# Monitor.net
KiCad netlist of a schematic drawn in EAGLE
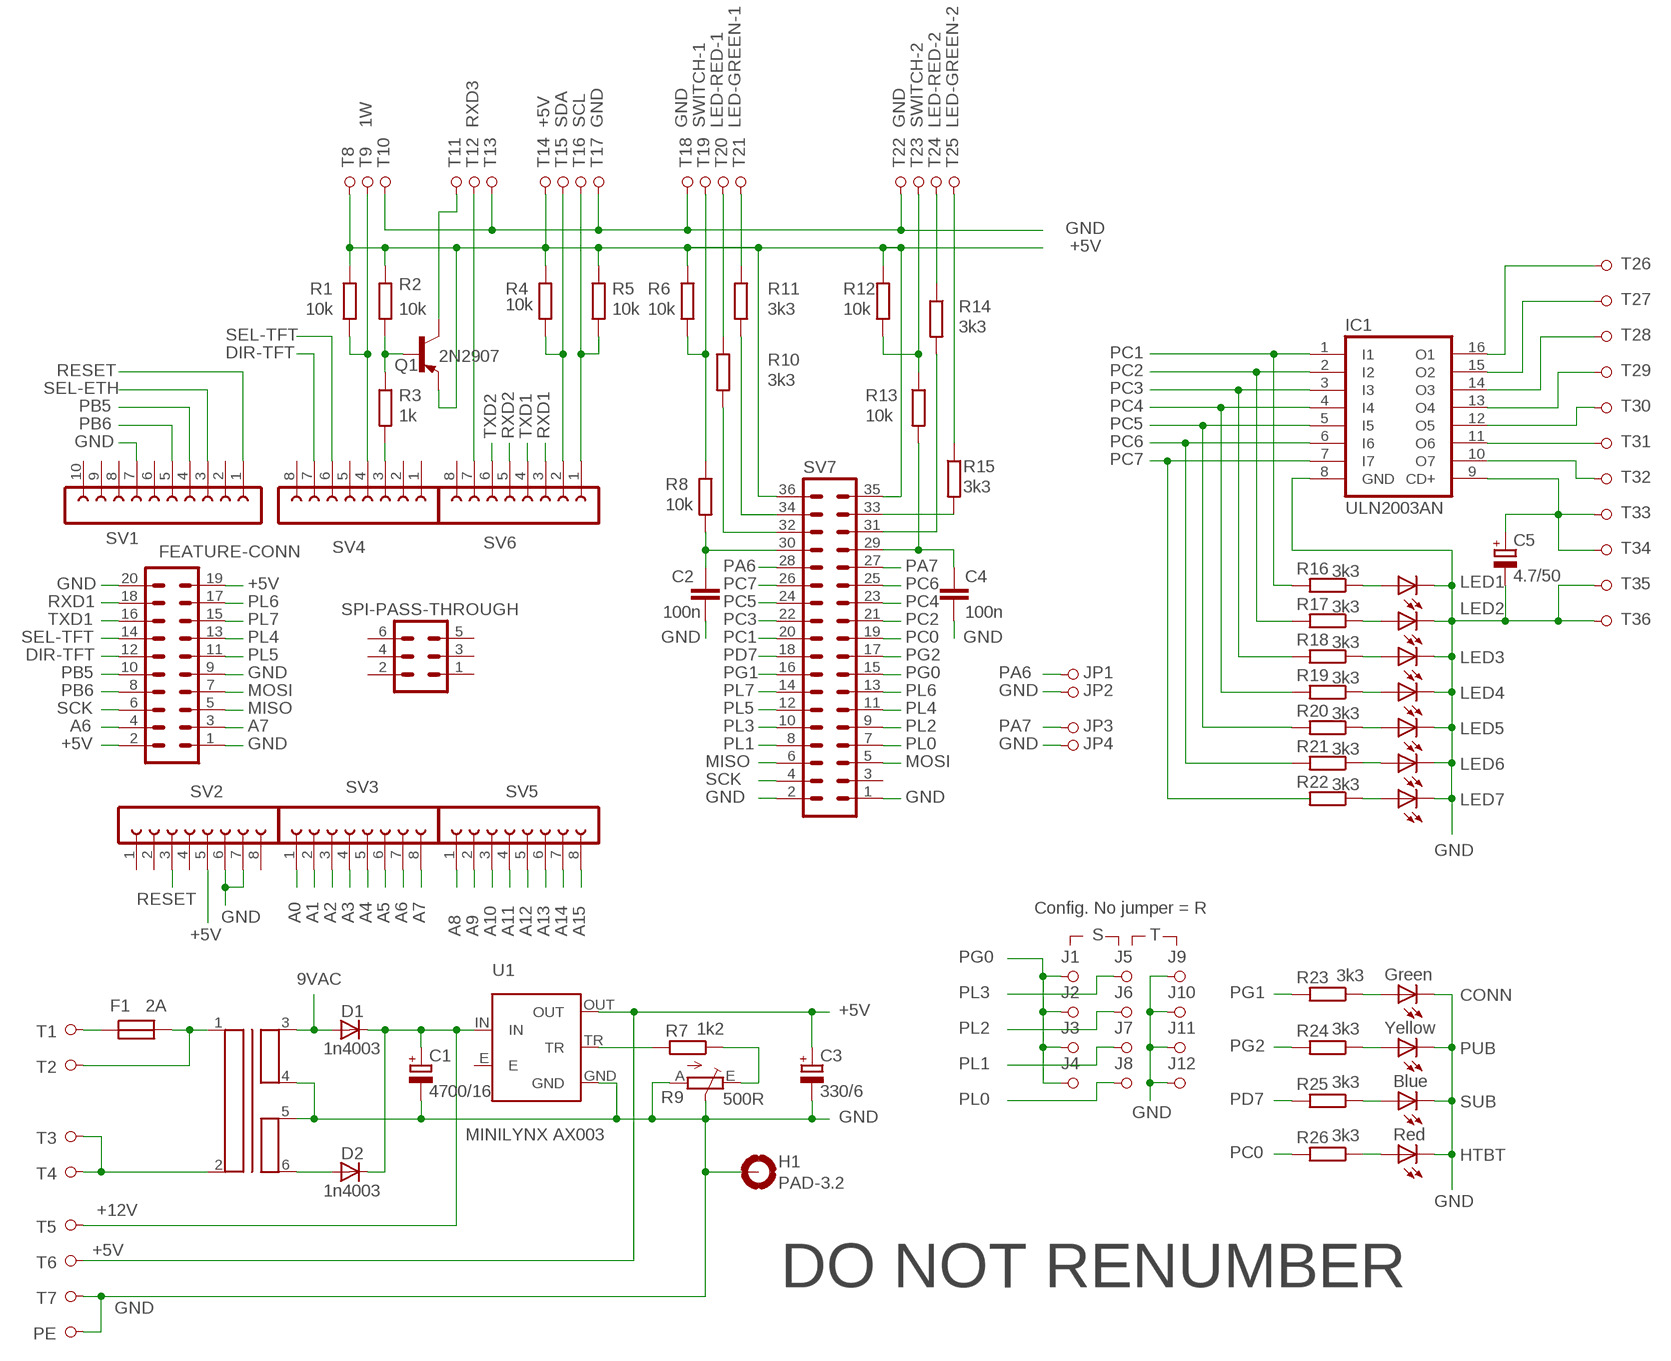
[diagram p0: schematic, sheet 1]
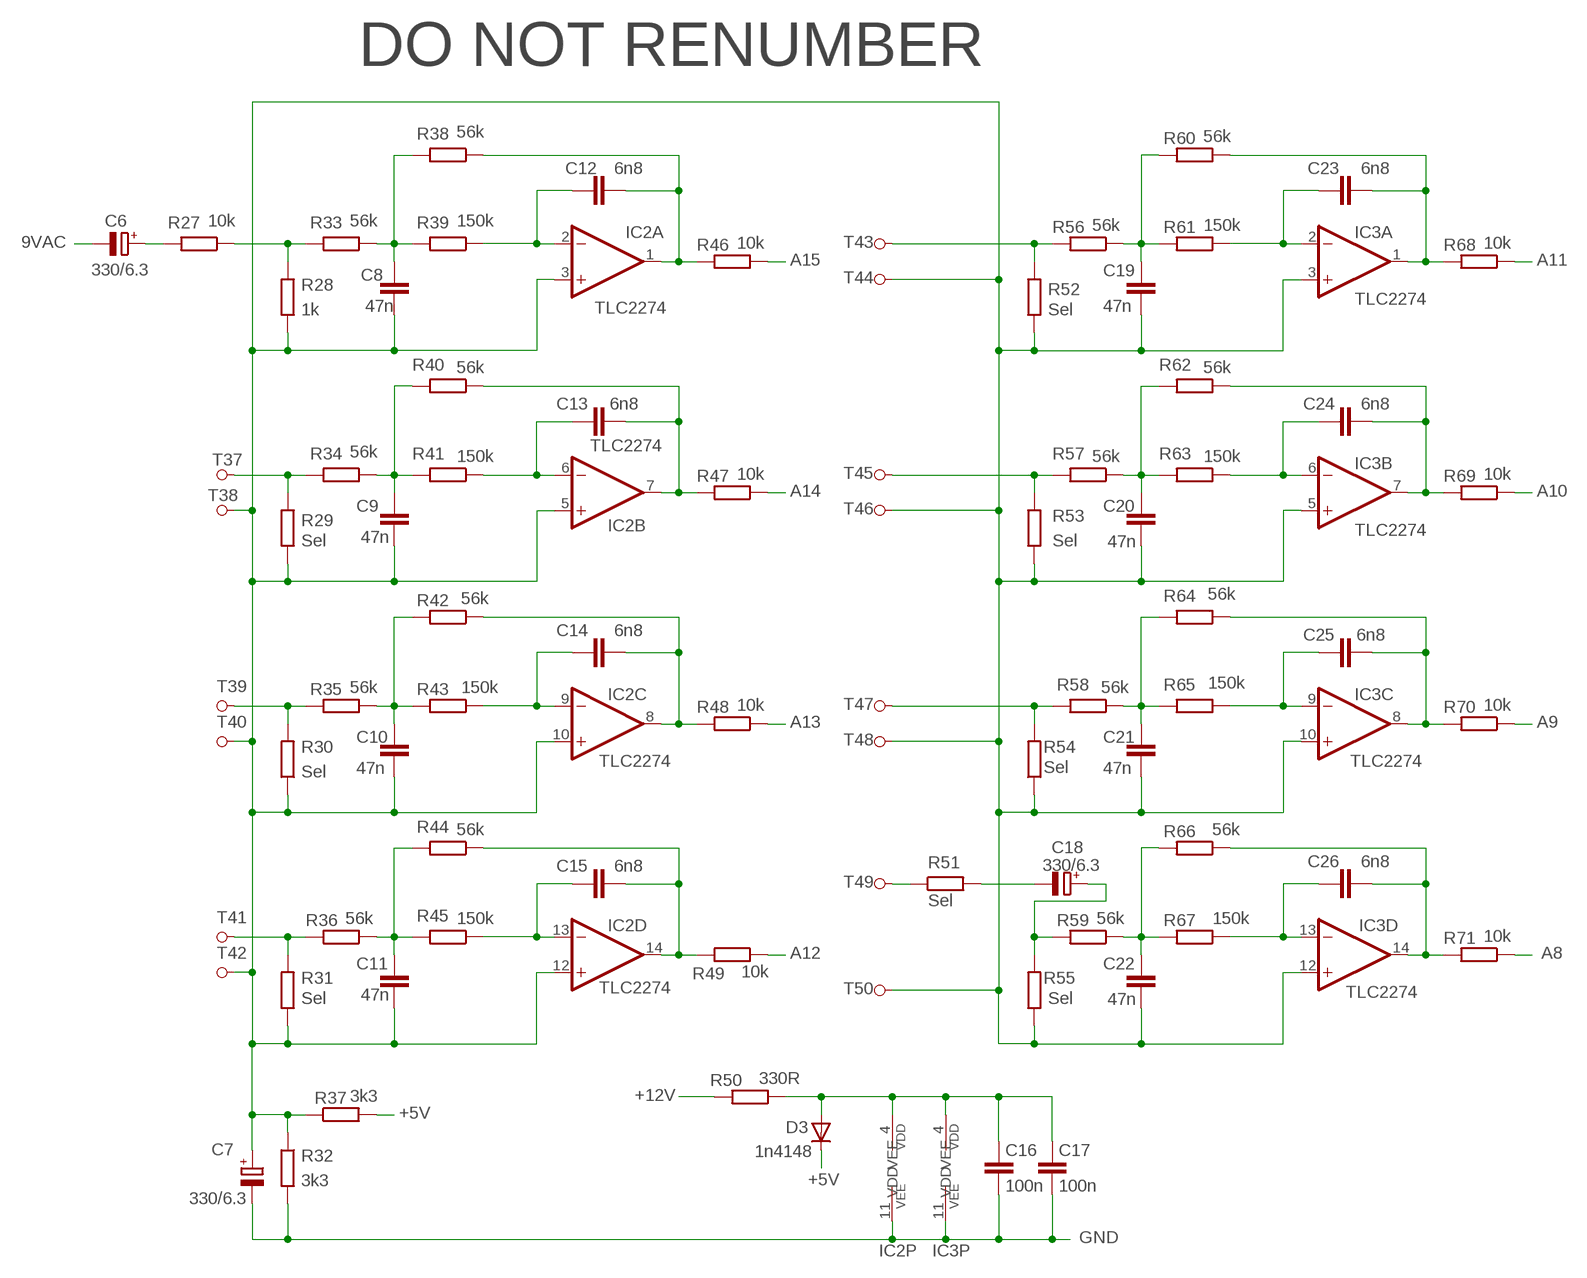
[diagram p1: schematic, sheet 2]

(export (version "E")
  (design (tool "Eeschema 10.0.6"))
  (components
    (comp (ref "C6")
      (value "330/6.3")
      (footprint "eagle-import:E2,5-7")
      (libsource (lib "eagle-import") (part "CPOL-EUE2.5-7"))
    )
    (comp (ref "C7")
      (value "330/6.3")
      (footprint "eagle-import:E2,5-7")
      (libsource (lib "eagle-import") (part "CPOL-EUE2.5-7"))
    )
    (comp (ref "C8")
      (value "47n")
      (footprint "eagle-import:C050-025X075")
      (libsource (lib "eagle-import") (part "C-EU050-025X075"))
    )
    (comp (ref "C9")
      (value "47n")
      (footprint "eagle-import:C050-025X075")
      (libsource (lib "eagle-import") (part "C-EU050-025X075"))
    )
    (comp (ref "C10")
      (value "47n")
      (footprint "eagle-import:C050-025X075")
      (libsource (lib "eagle-import") (part "C-EU050-025X075"))
    )
    (comp (ref "C11")
      (value "47n")
      (footprint "eagle-import:C050-025X075")
      (libsource (lib "eagle-import") (part "C-EU050-025X075"))
    )
    (comp (ref "C12")
      (value "6n8")
      (footprint "eagle-import:C050-025X075")
      (libsource (lib "eagle-import") (part "C-EU050-025X075"))
    )
    (comp (ref "C13")
      (value "6n8")
      (footprint "eagle-import:C050-025X075")
      (libsource (lib "eagle-import") (part "C-EU050-025X075"))
    )
    (comp (ref "C14")
      (value "6n8")
      (footprint "eagle-import:C050-025X075")
      (libsource (lib "eagle-import") (part "C-EU050-025X075"))
    )
    (comp (ref "C15")
      (value "6n8")
      (footprint "eagle-import:C050-025X075")
      (libsource (lib "eagle-import") (part "C-EU050-025X075"))
    )
    (comp (ref "C16")
      (value "100n")
      (footprint "eagle-import:C050-024X044")
      (libsource (lib "eagle-import") (part "C-EU050-024X044"))
    )
    (comp (ref "C17")
      (value "100n")
      (footprint "eagle-import:C050-024X044")
      (libsource (lib "eagle-import") (part "C-EU050-024X044"))
    )
    (comp (ref "C18")
      (value "330/6.3")
      (footprint "eagle-import:E2,5-7")
      (libsource (lib "eagle-import") (part "CPOL-EUE2.5-7"))
    )
    (comp (ref "C19")
      (value "47n")
      (footprint "eagle-import:C050-025X075")
      (libsource (lib "eagle-import") (part "C-EU050-025X075"))
    )
    (comp (ref "C20")
      (value "47n")
      (footprint "eagle-import:C050-025X075")
      (libsource (lib "eagle-import") (part "C-EU050-025X075"))
    )
    (comp (ref "C21")
      (value "47n")
      (footprint "eagle-import:C050-025X075")
      (libsource (lib "eagle-import") (part "C-EU050-025X075"))
    )
    (comp (ref "C22")
      (value "47n")
      (footprint "eagle-import:C050-025X075")
      (libsource (lib "eagle-import") (part "C-EU050-025X075"))
    )
    (comp (ref "C23")
      (value "6n8")
      (footprint "eagle-import:C050-025X075")
      (libsource (lib "eagle-import") (part "C-EU050-025X075"))
    )
    (comp (ref "C24")
      (value "6n8")
      (footprint "eagle-import:C050-025X075")
      (libsource (lib "eagle-import") (part "C-EU050-025X075"))
    )
    (comp (ref "C25")
      (value "6n8")
      (footprint "eagle-import:C050-025X075")
      (libsource (lib "eagle-import") (part "C-EU050-025X075"))
    )
    (comp (ref "C26")
      (value "6n8")
      (footprint "eagle-import:C050-025X075")
      (libsource (lib "eagle-import") (part "C-EU050-025X075"))
    )
    (comp (ref "D3")
      (value "1n4148")
      (footprint "eagle-import:DO34Z7")
      (libsource (lib "eagle-import") (part "1N4148"))
    )
    (comp (ref "IC2")
      (value "TLC2274")
      (footprint "eagle-import:DIL14")
      (libsource (lib "eagle-import") (part "LM124NC"))
    )
    (comp (ref "IC3")
      (value "TLC2274")
      (footprint "eagle-import:DIL14")
      (libsource (lib "eagle-import") (part "LM124NC"))
    )
    (comp (ref "R27")
      (value "10k")
      (footprint "eagle-import:0207_10")
      (libsource (lib "eagle-import") (part "R-EU_0207/10"))
    )
    (comp (ref "R28")
      (value "1k")
      (footprint "eagle-import:0207_10")
      (libsource (lib "eagle-import") (part "R-EU_0207/10"))
    )
    (comp (ref "R29")
      (value "Sel")
      (footprint "eagle-import:0207_10")
      (libsource (lib "eagle-import") (part "R-EU_0207/10"))
    )
    (comp (ref "R30")
      (value "Sel")
      (footprint "eagle-import:0207_10")
      (libsource (lib "eagle-import") (part "R-EU_0207/10"))
    )
    (comp (ref "R31")
      (value "Sel")
      (footprint "eagle-import:0207_10")
      (libsource (lib "eagle-import") (part "R-EU_0207/10"))
    )
    (comp (ref "R32")
      (value "3k3")
      (footprint "eagle-import:0207_10")
      (libsource (lib "eagle-import") (part "R-EU_0207/10"))
    )
    (comp (ref "R33")
      (value "56k")
      (footprint "eagle-import:0207_10")
      (libsource (lib "eagle-import") (part "R-EU_0207/10"))
    )
    (comp (ref "R34")
      (value "56k")
      (footprint "eagle-import:0207_10")
      (libsource (lib "eagle-import") (part "R-EU_0207/10"))
    )
    (comp (ref "R35")
      (value "56k")
      (footprint "eagle-import:0207_10")
      (libsource (lib "eagle-import") (part "R-EU_0207/10"))
    )
    (comp (ref "R36")
      (value "56k")
      (footprint "eagle-import:0207_10")
      (libsource (lib "eagle-import") (part "R-EU_0207/10"))
    )
    (comp (ref "R37")
      (value "3k3")
      (footprint "eagle-import:0207_10")
      (libsource (lib "eagle-import") (part "R-EU_0207/10"))
    )
    (comp (ref "R38")
      (value "56k")
      (footprint "eagle-import:0207_10")
      (libsource (lib "eagle-import") (part "R-EU_0207/10"))
    )
    (comp (ref "R39")
      (value "150k")
      (footprint "eagle-import:0207_10")
      (libsource (lib "eagle-import") (part "R-EU_0207/10"))
    )
    (comp (ref "R40")
      (value "56k")
      (footprint "eagle-import:0207_10")
      (libsource (lib "eagle-import") (part "R-EU_0207/10"))
    )
    (comp (ref "R41")
      (value "150k")
      (footprint "eagle-import:0207_10")
      (libsource (lib "eagle-import") (part "R-EU_0207/10"))
    )
    (comp (ref "R42")
      (value "56k")
      (footprint "eagle-import:0207_10")
      (libsource (lib "eagle-import") (part "R-EU_0207/10"))
    )
    (comp (ref "R43")
      (value "150k")
      (footprint "eagle-import:0207_10")
      (libsource (lib "eagle-import") (part "R-EU_0207/10"))
    )
    (comp (ref "R44")
      (value "56k")
      (footprint "eagle-import:0207_10")
      (libsource (lib "eagle-import") (part "R-EU_0207/10"))
    )
    (comp (ref "R45")
      (value "150k")
      (footprint "eagle-import:0207_10")
      (libsource (lib "eagle-import") (part "R-EU_0207/10"))
    )
    (comp (ref "R46")
      (value "10k")
      (footprint "eagle-import:0207_10")
      (libsource (lib "eagle-import") (part "R-EU_0207/10"))
    )
    (comp (ref "R47")
      (value "10k")
      (footprint "eagle-import:0207_10")
      (libsource (lib "eagle-import") (part "R-EU_0207/10"))
    )
    (comp (ref "R48")
      (value "10k")
      (footprint "eagle-import:0207_10")
      (libsource (lib "eagle-import") (part "R-EU_0207/10"))
    )
    (comp (ref "R49")
      (value "10k")
      (footprint "eagle-import:0207_10")
      (libsource (lib "eagle-import") (part "R-EU_0207/10"))
    )
    (comp (ref "R50")
      (value "330R")
      (footprint "eagle-import:0207_10")
      (libsource (lib "eagle-import") (part "R-EU_0207/10"))
    )
    (comp (ref "R51")
      (value "Sel")
      (footprint "eagle-import:0207_10")
      (libsource (lib "eagle-import") (part "R-EU_0207/10"))
    )
    (comp (ref "R52")
      (value "Sel")
      (footprint "eagle-import:0207_10")
      (libsource (lib "eagle-import") (part "R-EU_0207/10"))
    )
    (comp (ref "R53")
      (value "Sel")
      (footprint "eagle-import:0207_10")
      (libsource (lib "eagle-import") (part "R-EU_0207/10"))
    )
    (comp (ref "R54")
      (value "Sel")
      (footprint "eagle-import:0207_10")
      (libsource (lib "eagle-import") (part "R-EU_0207/10"))
    )
    (comp (ref "R55")
      (value "Sel")
      (footprint "eagle-import:0207_10")
      (libsource (lib "eagle-import") (part "R-EU_0207/10"))
    )
    (comp (ref "R56")
      (value "56k")
      (footprint "eagle-import:0207_10")
      (libsource (lib "eagle-import") (part "R-EU_0207/10"))
    )
    (comp (ref "R57")
      (value "56k")
      (footprint "eagle-import:0207_10")
      (libsource (lib "eagle-import") (part "R-EU_0207/10"))
    )
    (comp (ref "R58")
      (value "56k")
      (footprint "eagle-import:0207_10")
      (libsource (lib "eagle-import") (part "R-EU_0207/10"))
    )
    (comp (ref "R59")
      (value "56k")
      (footprint "eagle-import:0207_10")
      (libsource (lib "eagle-import") (part "R-EU_0207/10"))
    )
    (comp (ref "R60")
      (value "56k")
      (footprint "eagle-import:0207_10")
      (libsource (lib "eagle-import") (part "R-EU_0207/10"))
    )
    (comp (ref "R61")
      (value "150k")
      (footprint "eagle-import:0207_10")
      (libsource (lib "eagle-import") (part "R-EU_0207/10"))
    )
    (comp (ref "R62")
      (value "56k")
      (footprint "eagle-import:0207_10")
      (libsource (lib "eagle-import") (part "R-EU_0207/10"))
    )
    (comp (ref "R63")
      (value "150k")
      (footprint "eagle-import:0207_10")
      (libsource (lib "eagle-import") (part "R-EU_0207/10"))
    )
    (comp (ref "R64")
      (value "56k")
      (footprint "eagle-import:0207_10")
      (libsource (lib "eagle-import") (part "R-EU_0207/10"))
    )
    (comp (ref "R65")
      (value "150k")
      (footprint "eagle-import:0207_10")
      (libsource (lib "eagle-import") (part "R-EU_0207/10"))
    )
    (comp (ref "R66")
      (value "56k")
      (footprint "eagle-import:0207_10")
      (libsource (lib "eagle-import") (part "R-EU_0207/10"))
    )
    (comp (ref "R67")
      (value "150k")
      (footprint "eagle-import:0207_10")
      (libsource (lib "eagle-import") (part "R-EU_0207/10"))
    )
    (comp (ref "R68")
      (value "10k")
      (footprint "eagle-import:0207_10")
      (libsource (lib "eagle-import") (part "R-EU_0207/10"))
    )
    (comp (ref "R69")
      (value "10k")
      (footprint "eagle-import:0207_10")
      (libsource (lib "eagle-import") (part "R-EU_0207/10"))
    )
    (comp (ref "R70")
      (value "10k")
      (footprint "eagle-import:0207_10")
      (libsource (lib "eagle-import") (part "R-EU_0207/10"))
    )
    (comp (ref "R71")
      (value "10k")
      (footprint "eagle-import:0207_10")
      (libsource (lib "eagle-import") (part "R-EU_0207/10"))
    )
    (comp (ref "T37")
      (value "PINHDR-1X1")
      (footprint "eagle-import:HDR1X1")
      (libsource (lib "eagle-import") (part "PINHDR-1X1"))
    )
    (comp (ref "T38")
      (value "PINHDR-1X1")
      (footprint "eagle-import:HDR1X1")
      (libsource (lib "eagle-import") (part "PINHDR-1X1"))
    )
    (comp (ref "T39")
      (value "PINHDR-1X1")
      (footprint "eagle-import:HDR1X1")
      (libsource (lib "eagle-import") (part "PINHDR-1X1"))
    )
    (comp (ref "T40")
      (value "PINHDR-1X1")
      (footprint "eagle-import:HDR1X1")
      (libsource (lib "eagle-import") (part "PINHDR-1X1"))
    )
    (comp (ref "T41")
      (value "PINHDR-1X1")
      (footprint "eagle-import:HDR1X1")
      (libsource (lib "eagle-import") (part "PINHDR-1X1"))
    )
    (comp (ref "T42")
      (value "PINHDR-1X1")
      (footprint "eagle-import:HDR1X1")
      (libsource (lib "eagle-import") (part "PINHDR-1X1"))
    )
    (comp (ref "T43")
      (value "PINHDR-1X1")
      (footprint "eagle-import:HDR1X1")
      (libsource (lib "eagle-import") (part "PINHDR-1X1"))
    )
    (comp (ref "T44")
      (value "PINHDR-1X1")
      (footprint "eagle-import:HDR1X1")
      (libsource (lib "eagle-import") (part "PINHDR-1X1"))
    )
    (comp (ref "T45")
      (value "PINHDR-1X1")
      (footprint "eagle-import:HDR1X1")
      (libsource (lib "eagle-import") (part "PINHDR-1X1"))
    )
    (comp (ref "T46")
      (value "PINHDR-1X1")
      (footprint "eagle-import:HDR1X1")
      (libsource (lib "eagle-import") (part "PINHDR-1X1"))
    )
    (comp (ref "T47")
      (value "PINHDR-1X1")
      (footprint "eagle-import:HDR1X1")
      (libsource (lib "eagle-import") (part "PINHDR-1X1"))
    )
    (comp (ref "T48")
      (value "PINHDR-1X1")
      (footprint "eagle-import:HDR1X1")
      (libsource (lib "eagle-import") (part "PINHDR-1X1"))
    )
    (comp (ref "T49")
      (value "PINHDR-1X1")
      (footprint "eagle-import:HDR1X1")
      (libsource (lib "eagle-import") (part "PINHDR-1X1"))
    )
    (comp (ref "T50")
      (value "PINHDR-1X1")
      (footprint "eagle-import:HDR1X1")
      (libsource (lib "eagle-import") (part "PINHDR-1X1"))
    )
    (comp (ref "C1")
      (value "4700/16")
      (footprint "eagle-import:E7,5-16")
      (libsource (lib "eagle-import") (part "CPOL-EUE7.5-16"))
    )
    (comp (ref "C2")
      (value "100n")
      (footprint "eagle-import:C050-024X044")
      (libsource (lib "eagle-import") (part "C-EU050-024X044"))
    )
    (comp (ref "C3")
      (value "330/6")
      (footprint "eagle-import:E2,5-7")
      (libsource (lib "eagle-import") (part "CPOL-EUE2.5-7"))
    )
    (comp (ref "C4")
      (value "100n")
      (footprint "eagle-import:C050-024X044")
      (libsource (lib "eagle-import") (part "C-EU050-024X044"))
    )
    (comp (ref "C5")
      (value "4.7/50")
      (footprint "eagle-import:E5-5")
      (libsource (lib "eagle-import") (part "CPOL-EUE5-5"))
    )
    (comp (ref "CONN")
      (value "Green")
      (footprint "eagle-import:LED3MM")
      (libsource (lib "eagle-import") (part "LED3MM"))
    )
    (comp (ref "D1")
      (value "1n4003")
      (footprint "eagle-import:DO34Z7")
      (libsource (lib "eagle-import") (part "1N4148"))
    )
    (comp (ref "D2")
      (value "1n4003")
      (footprint "eagle-import:DO34Z7")
      (libsource (lib "eagle-import") (part "1N4148"))
    )
    (comp (ref "F1")
      (value "2A")
      (footprint "eagle-import:FX0456")
      (libsource (lib "eagle-import") (part "FX0456-ZEKERING"))
    )
    (comp (ref "FEATURE-CONN")
      (value "PINHD-10X2")
      (footprint "eagle-import:MA10-2")
      (libsource (lib "eagle-import") (part "PINHD-10X2"))
    )
    (comp (ref "H1")
      (value "PAD-3.2")
      (footprint "eagle-import:3,2-PAD")
      (libsource (lib "eagle-import") (part "MOUNT-PAD-ROUND3.2"))
    )
    (comp (ref "HTBT")
      (value "Red")
      (footprint "eagle-import:LED3MM")
      (libsource (lib "eagle-import") (part "LED3MM"))
    )
    (comp (ref "IC1")
      (value "ULN2003AN")
      (footprint "eagle-import:DIL16")
      (libsource (lib "eagle-import") (part "ULN2003AN"))
    )
    (comp (ref "J1")
      (value "PINHDR-1X1")
      (footprint "eagle-import:HDR1X1")
      (libsource (lib "eagle-import") (part "PINHDR-1X1"))
    )
    (comp (ref "J2")
      (value "PINHDR-1X1")
      (footprint "eagle-import:HDR1X1")
      (libsource (lib "eagle-import") (part "PINHDR-1X1"))
    )
    (comp (ref "J3")
      (value "PINHDR-1X1")
      (footprint "eagle-import:HDR1X1")
      (libsource (lib "eagle-import") (part "PINHDR-1X1"))
    )
    (comp (ref "J4")
      (value "PINHDR-1X1")
      (footprint "eagle-import:HDR1X1")
      (libsource (lib "eagle-import") (part "PINHDR-1X1"))
    )
    (comp (ref "J5")
      (value "PINHDR-1X1")
      (footprint "eagle-import:HDR1X1")
      (libsource (lib "eagle-import") (part "PINHDR-1X1"))
    )
    (comp (ref "J6")
      (value "PINHDR-1X1")
      (footprint "eagle-import:HDR1X1")
      (libsource (lib "eagle-import") (part "PINHDR-1X1"))
    )
    (comp (ref "J7")
      (value "PINHDR-1X1")
      (footprint "eagle-import:HDR1X1")
      (libsource (lib "eagle-import") (part "PINHDR-1X1"))
    )
    (comp (ref "J8")
      (value "PINHDR-1X1")
      (footprint "eagle-import:HDR1X1")
      (libsource (lib "eagle-import") (part "PINHDR-1X1"))
    )
    (comp (ref "J9")
      (value "PINHDR-1X1")
      (footprint "eagle-import:HDR1X1")
      (libsource (lib "eagle-import") (part "PINHDR-1X1"))
    )
    (comp (ref "J10")
      (value "PINHDR-1X1")
      (footprint "eagle-import:HDR1X1")
      (libsource (lib "eagle-import") (part "PINHDR-1X1"))
    )
    (comp (ref "J11")
      (value "PINHDR-1X1")
      (footprint "eagle-import:HDR1X1")
      (libsource (lib "eagle-import") (part "PINHDR-1X1"))
    )
    (comp (ref "J12")
      (value "PINHDR-1X1")
      (footprint "eagle-import:HDR1X1")
      (libsource (lib "eagle-import") (part "PINHDR-1X1"))
    )
    (comp (ref "JP1")
      (value "PINHDR-1X1")
      (footprint "eagle-import:HDR1X1")
      (libsource (lib "eagle-import") (part "PINHDR-1X1"))
    )
    (comp (ref "JP2")
      (value "PINHDR-1X1")
      (footprint "eagle-import:HDR1X1")
      (libsource (lib "eagle-import") (part "PINHDR-1X1"))
    )
    (comp (ref "JP3")
      (value "PINHDR-1X1")
      (footprint "eagle-import:HDR1X1")
      (libsource (lib "eagle-import") (part "PINHDR-1X1"))
    )
    (comp (ref "JP4")
      (value "PINHDR-1X1")
      (footprint "eagle-import:HDR1X1")
      (libsource (lib "eagle-import") (part "PINHDR-1X1"))
    )
    (comp (ref "LED1")
      (value "LED3MM")
      (footprint "eagle-import:LED3MM")
      (libsource (lib "eagle-import") (part "LED3MM"))
    )
    (comp (ref "LED2")
      (value "LED3MM")
      (footprint "eagle-import:LED3MM")
      (libsource (lib "eagle-import") (part "LED3MM"))
    )
    (comp (ref "LED3")
      (value "LED3MM")
      (footprint "eagle-import:LED3MM")
      (libsource (lib "eagle-import") (part "LED3MM"))
    )
    (comp (ref "LED4")
      (value "LED3MM")
      (footprint "eagle-import:LED3MM")
      (libsource (lib "eagle-import") (part "LED3MM"))
    )
    (comp (ref "LED5")
      (value "LED3MM")
      (footprint "eagle-import:LED3MM")
      (libsource (lib "eagle-import") (part "LED3MM"))
    )
    (comp (ref "LED6")
      (value "LED3MM")
      (footprint "eagle-import:LED3MM")
      (libsource (lib "eagle-import") (part "LED3MM"))
    )
    (comp (ref "LED7")
      (value "LED3MM")
      (footprint "eagle-import:LED3MM")
      (libsource (lib "eagle-import") (part "LED3MM"))
    )
    (comp (ref "PE")
      (value "PINHDR-1X1")
      (footprint "eagle-import:HDR1X1")
      (libsource (lib "eagle-import") (part "PINHDR-1X1"))
    )
    (comp (ref "PUB")
      (value "Yellow")
      (footprint "eagle-import:LED3MM")
      (libsource (lib "eagle-import") (part "LED3MM"))
    )
    (comp (ref "Q1")
      (value "2N2907")
      (footprint "eagle-import:TO39")
      (libsource (lib "eagle-import") (part "PNP-TO39"))
    )
    (comp (ref "R1")
      (value "10k")
      (footprint "eagle-import:0207_10")
      (libsource (lib "eagle-import") (part "R-EU_0207/10"))
    )
    (comp (ref "R2")
      (value "10k")
      (footprint "eagle-import:0207_10")
      (libsource (lib "eagle-import") (part "R-EU_0207/10"))
    )
    (comp (ref "R3")
      (value "1k")
      (footprint "eagle-import:0207_10")
      (libsource (lib "eagle-import") (part "R-EU_0207/10"))
    )
    (comp (ref "R4")
      (value "10k")
      (footprint "eagle-import:0207_10")
      (libsource (lib "eagle-import") (part "R-EU_0207/10"))
    )
    (comp (ref "R5")
      (value "10k")
      (footprint "eagle-import:0207_10")
      (libsource (lib "eagle-import") (part "R-EU_0207/10"))
    )
    (comp (ref "R6")
      (value "10k")
      (footprint "eagle-import:0207_10")
      (libsource (lib "eagle-import") (part "R-EU_0207/10"))
    )
    (comp (ref "R7")
      (value "1k2")
      (footprint "eagle-import:0207_10")
      (libsource (lib "eagle-import") (part "R-EU_0207/10"))
    )
    (comp (ref "R8")
      (value "10k")
      (footprint "eagle-import:0207_10")
      (libsource (lib "eagle-import") (part "R-EU_0207/10"))
    )
    (comp (ref "R9")
      (value "500R")
      (footprint "eagle-import:TRIMPOT-4")
      (libsource (lib "eagle-import") (part "TRIMPOT-4"))
    )
    (comp (ref "R10")
      (value "3k3")
      (footprint "eagle-import:0207_10")
      (libsource (lib "eagle-import") (part "R-EU_0207/10"))
    )
    (comp (ref "R11")
      (value "3k3")
      (footprint "eagle-import:0207_10")
      (libsource (lib "eagle-import") (part "R-EU_0207/10"))
    )
    (comp (ref "R12")
      (value "10k")
      (footprint "eagle-import:0207_10")
      (libsource (lib "eagle-import") (part "R-EU_0207/10"))
    )
    (comp (ref "R13")
      (value "10k")
      (footprint "eagle-import:0207_10")
      (libsource (lib "eagle-import") (part "R-EU_0207/10"))
    )
    (comp (ref "R14")
      (value "3k3")
      (footprint "eagle-import:0207_10")
      (libsource (lib "eagle-import") (part "R-EU_0207/10"))
    )
    (comp (ref "R15")
      (value "3k3")
      (footprint "eagle-import:0207_10")
      (libsource (lib "eagle-import") (part "R-EU_0207/10"))
    )
    (comp (ref "R16")
      (value "3k3")
      (footprint "eagle-import:0207_10")
      (libsource (lib "eagle-import") (part "R-EU_0207/10"))
    )
    (comp (ref "R17")
      (value "3k3")
      (footprint "eagle-import:0207_10")
      (libsource (lib "eagle-import") (part "R-EU_0207/10"))
    )
    (comp (ref "R18")
      (value "3k3")
      (footprint "eagle-import:0207_10")
      (libsource (lib "eagle-import") (part "R-EU_0207/10"))
    )
    (comp (ref "R19")
      (value "3k3")
      (footprint "eagle-import:0207_10")
      (libsource (lib "eagle-import") (part "R-EU_0207/10"))
    )
    (comp (ref "R20")
      (value "3k3")
      (footprint "eagle-import:0207_10")
      (libsource (lib "eagle-import") (part "R-EU_0207/10"))
    )
    (comp (ref "R21")
      (value "3k3")
      (footprint "eagle-import:0207_10")
      (libsource (lib "eagle-import") (part "R-EU_0207/10"))
    )
    (comp (ref "R22")
      (value "3k3")
      (footprint "eagle-import:0207_10")
      (libsource (lib "eagle-import") (part "R-EU_0207/10"))
    )
    (comp (ref "R23")
      (value "3k3")
      (footprint "eagle-import:0207_10")
      (libsource (lib "eagle-import") (part "R-EU_0207/10"))
    )
    (comp (ref "R24")
      (value "3k3")
      (footprint "eagle-import:0207_10")
      (libsource (lib "eagle-import") (part "R-EU_0207/10"))
    )
    (comp (ref "R25")
      (value "3k3")
      (footprint "eagle-import:0207_10")
      (libsource (lib "eagle-import") (part "R-EU_0207/10"))
    )
    (comp (ref "R26")
      (value "3k3")
      (footprint "eagle-import:0207_10")
      (libsource (lib "eagle-import") (part "R-EU_0207/10"))
    )
    (comp (ref "SPI-PASS-THROUGH")
      (value "PINHD-3X2")
      (footprint "eagle-import:MA03-2")
      (libsource (lib "eagle-import") (part "PINHD-3X2"))
    )
    (comp (ref "SUB")
      (value "Blue")
      (footprint "eagle-import:LED3MM")
      (libsource (lib "eagle-import") (part "LED3MM"))
    )
    (comp (ref "SV1")
      (value "FE10-1")
      (footprint "eagle-import:FE10")
      (libsource (lib "eagle-import") (part "FE10-1"))
    )
    (comp (ref "SV2")
      (value "FE08-1")
      (footprint "eagle-import:FE08")
      (libsource (lib "eagle-import") (part "FE08-1"))
    )
    (comp (ref "SV3")
      (value "FE08-1")
      (footprint "eagle-import:FE08")
      (libsource (lib "eagle-import") (part "FE08-1"))
    )
    (comp (ref "SV4")
      (value "FE08-1")
      (footprint "eagle-import:FE08")
      (libsource (lib "eagle-import") (part "FE08-1"))
    )
    (comp (ref "SV5")
      (value "FE08-1")
      (footprint "eagle-import:FE08")
      (libsource (lib "eagle-import") (part "FE08-1"))
    )
    (comp (ref "SV6")
      (value "FE08-1")
      (footprint "eagle-import:FE08")
      (libsource (lib "eagle-import") (part "FE08-1"))
    )
    (comp (ref "SV7")
      (value "PINHD-18X2")
      (footprint "eagle-import:MA18-2")
      (libsource (lib "eagle-import") (part "PINHD-18X2"))
    )
    (comp (ref "T1")
      (value "PINHDR-1X1")
      (footprint "eagle-import:HDR1X1")
      (libsource (lib "eagle-import") (part "PINHDR-1X1"))
    )
    (comp (ref "T2")
      (value "PINHDR-1X1")
      (footprint "eagle-import:HDR1X1")
      (libsource (lib "eagle-import") (part "PINHDR-1X1"))
    )
    (comp (ref "T3")
      (value "PINHDR-1X1")
      (footprint "eagle-import:HDR1X1")
      (libsource (lib "eagle-import") (part "PINHDR-1X1"))
    )
    (comp (ref "T4")
      (value "PINHDR-1X1")
      (footprint "eagle-import:HDR1X1")
      (libsource (lib "eagle-import") (part "PINHDR-1X1"))
    )
    (comp (ref "T5")
      (value "PINHDR-1X1")
      (footprint "eagle-import:HDR1X1")
      (libsource (lib "eagle-import") (part "PINHDR-1X1"))
    )
    (comp (ref "T6")
      (value "PINHDR-1X1")
      (footprint "eagle-import:HDR1X1")
      (libsource (lib "eagle-import") (part "PINHDR-1X1"))
    )
    (comp (ref "T7")
      (value "PINHDR-1X1")
      (footprint "eagle-import:HDR1X1")
      (libsource (lib "eagle-import") (part "PINHDR-1X1"))
    )
    (comp (ref "T8")
      (value "PINHDR-1X1")
      (footprint "eagle-import:HDR1X1")
      (libsource (lib "eagle-import") (part "PINHDR-1X1"))
    )
    (comp (ref "T9")
      (value "PINHDR-1X1")
      (footprint "eagle-import:HDR1X1")
      (libsource (lib "eagle-import") (part "PINHDR-1X1"))
    )
    (comp (ref "T10")
      (value "PINHDR-1X1")
      (footprint "eagle-import:HDR1X1")
      (libsource (lib "eagle-import") (part "PINHDR-1X1"))
    )
    (comp (ref "T11")
      (value "PINHDR-1X1")
      (footprint "eagle-import:HDR1X1")
      (libsource (lib "eagle-import") (part "PINHDR-1X1"))
    )
    (comp (ref "T12")
      (value "PINHDR-1X1")
      (footprint "eagle-import:HDR1X1")
      (libsource (lib "eagle-import") (part "PINHDR-1X1"))
    )
    (comp (ref "T13")
      (value "PINHDR-1X1")
      (footprint "eagle-import:HDR1X1")
      (libsource (lib "eagle-import") (part "PINHDR-1X1"))
    )
    (comp (ref "T14")
      (value "PINHDR-1X1")
      (footprint "eagle-import:HDR1X1")
      (libsource (lib "eagle-import") (part "PINHDR-1X1"))
    )
    (comp (ref "T15")
      (value "PINHDR-1X1")
      (footprint "eagle-import:HDR1X1")
      (libsource (lib "eagle-import") (part "PINHDR-1X1"))
    )
    (comp (ref "T16")
      (value "PINHDR-1X1")
      (footprint "eagle-import:HDR1X1")
      (libsource (lib "eagle-import") (part "PINHDR-1X1"))
    )
    (comp (ref "T17")
      (value "PINHDR-1X1")
      (footprint "eagle-import:HDR1X1")
      (libsource (lib "eagle-import") (part "PINHDR-1X1"))
    )
    (comp (ref "T18")
      (value "PINHDR-1X1")
      (footprint "eagle-import:HDR1X1")
      (libsource (lib "eagle-import") (part "PINHDR-1X1"))
    )
    (comp (ref "T19")
      (value "PINHDR-1X1")
      (footprint "eagle-import:HDR1X1")
      (libsource (lib "eagle-import") (part "PINHDR-1X1"))
    )
    (comp (ref "T20")
      (value "PINHDR-1X1")
      (footprint "eagle-import:HDR1X1")
      (libsource (lib "eagle-import") (part "PINHDR-1X1"))
    )
    (comp (ref "T21")
      (value "PINHDR-1X1")
      (footprint "eagle-import:HDR1X1")
      (libsource (lib "eagle-import") (part "PINHDR-1X1"))
    )
    (comp (ref "T22")
      (value "PINHDR-1X1")
      (footprint "eagle-import:HDR1X1")
      (libsource (lib "eagle-import") (part "PINHDR-1X1"))
    )
    (comp (ref "T23")
      (value "PINHDR-1X1")
      (footprint "eagle-import:HDR1X1")
      (libsource (lib "eagle-import") (part "PINHDR-1X1"))
    )
    (comp (ref "T24")
      (value "PINHDR-1X1")
      (footprint "eagle-import:HDR1X1")
      (libsource (lib "eagle-import") (part "PINHDR-1X1"))
    )
    (comp (ref "T25")
      (value "PINHDR-1X1")
      (footprint "eagle-import:HDR1X1")
      (libsource (lib "eagle-import") (part "PINHDR-1X1"))
    )
    (comp (ref "T26")
      (value "PINHDR-1X1")
      (footprint "eagle-import:HDR1X1")
      (libsource (lib "eagle-import") (part "PINHDR-1X1"))
    )
    (comp (ref "T27")
      (value "PINHDR-1X1")
      (footprint "eagle-import:HDR1X1")
      (libsource (lib "eagle-import") (part "PINHDR-1X1"))
    )
    (comp (ref "T28")
      (value "PINHDR-1X1")
      (footprint "eagle-import:HDR1X1")
      (libsource (lib "eagle-import") (part "PINHDR-1X1"))
    )
    (comp (ref "T29")
      (value "PINHDR-1X1")
      (footprint "eagle-import:HDR1X1")
      (libsource (lib "eagle-import") (part "PINHDR-1X1"))
    )
    (comp (ref "T30")
      (value "PINHDR-1X1")
      (footprint "eagle-import:HDR1X1")
      (libsource (lib "eagle-import") (part "PINHDR-1X1"))
    )
    (comp (ref "T31")
      (value "PINHDR-1X1")
      (footprint "eagle-import:HDR1X1")
      (libsource (lib "eagle-import") (part "PINHDR-1X1"))
    )
    (comp (ref "T32")
      (value "PINHDR-1X1")
      (footprint "eagle-import:HDR1X1")
      (libsource (lib "eagle-import") (part "PINHDR-1X1"))
    )
    (comp (ref "T33")
      (value "PINHDR-1X1")
      (footprint "eagle-import:HDR1X1")
      (libsource (lib "eagle-import") (part "PINHDR-1X1"))
    )
    (comp (ref "T34")
      (value "PINHDR-1X1")
      (footprint "eagle-import:HDR1X1")
      (libsource (lib "eagle-import") (part "PINHDR-1X1"))
    )
    (comp (ref "T35")
      (value "PINHDR-1X1")
      (footprint "eagle-import:HDR1X1")
      (libsource (lib "eagle-import") (part "PINHDR-1X1"))
    )
    (comp (ref "T36")
      (value "PINHDR-1X1")
      (footprint "eagle-import:HDR1X1")
      (libsource (lib "eagle-import") (part "PINHDR-1X1"))
    )
    (comp (ref "TR1")
      (value "TRAFO")
      (footprint "eagle-import:TRAFO")
      (libsource (lib "eagle-import") (part "TRAFO"))
    )
    (comp (ref "U1")
      (value "MINILYNX AX003")
      (footprint "eagle-import:MINILYNX")
      (libsource (lib "eagle-import") (part "MINILYNX"))
    )
  )
  (nets
    (net (code "1") (name "+5V") (class "Default")
      (node (ref "C3") (pin "+") (pinfunction "+_+") (pintype "passive"))
      (node (ref "D3") (pin "C") (pinfunction "C_C") (pintype "passive"))
      (node (ref "FEATURE-CONN") (pin "19") (pinfunction "19_19") (pintype "passive"))
      (node (ref "FEATURE-CONN") (pin "2") (pinfunction "2_2") (pintype "passive"))
      (node (ref "Q1") (pin "1") (pinfunction "E_1") (pintype "passive"))
      (node (ref "R1") (pin "1") (pinfunction "1_1") (pintype "passive"))
      (node (ref "R12") (pin "1") (pinfunction "1_1") (pintype "passive"))
      (node (ref "R2") (pin "1") (pinfunction "1_1") (pintype "passive"))
      (node (ref "R37") (pin "2") (pinfunction "2_2") (pintype "passive"))
      (node (ref "R4") (pin "1") (pinfunction "1_1") (pintype "passive"))
      (node (ref "R5") (pin "1") (pinfunction "1_1") (pintype "passive"))
      (node (ref "R6") (pin "1") (pinfunction "1_1") (pintype "passive"))
      (node (ref "SV2") (pin "5") (pinfunction "5_5") (pintype "passive"))
      (node (ref "SV7") (pin "35") (pinfunction "35_35") (pintype "passive"))
      (node (ref "SV7") (pin "36") (pinfunction "36_36") (pintype "passive"))
      (node (ref "T14") (pin "1") (pinfunction "._1") (pintype "passive"))
      (node (ref "T6") (pin "1") (pinfunction "._1") (pintype "passive"))
      (node (ref "T8") (pin "1") (pinfunction "._1") (pintype "passive"))
      (node (ref "U1") (pin "OUT") (pinfunction "OUT_OUT") (pintype "output"))
    )
    (net (code "2") (name "+12V") (class "Default")
      (node (ref "C1") (pin "+") (pinfunction "+_+") (pintype "passive"))
      (node (ref "D1") (pin "C") (pinfunction "C_C") (pintype "passive"))
      (node (ref "D2") (pin "C") (pinfunction "C_C") (pintype "passive"))
      (node (ref "R50") (pin "2") (pinfunction "2_2") (pintype "passive"))
      (node (ref "T5") (pin "1") (pinfunction "._1") (pintype "passive"))
      (node (ref "U1") (pin "IN") (pinfunction "IN_IN") (pintype "power_in"))
    )
    (net (code "3") (name "1W") (class "Default")
      (node (ref "R1") (pin "2") (pinfunction "2_2") (pintype "passive"))
      (node (ref "SV4") (pin "4") (pinfunction "4_4") (pintype "passive"))
      (node (ref "T9") (pin "1") (pinfunction "._1") (pintype "passive"))
    )
    (net (code "4") (name "9VAC") (class "Default")
      (node (ref "C6") (pin "-") (pinfunction "-_-") (pintype "passive"))
      (node (ref "D1") (pin "A") (pinfunction "A_A") (pintype "passive"))
      (node (ref "TR1") (pin "3") (pinfunction "3_3") (pintype "bidirectional"))
    )
    (net (code "5") (name "A0") (class "Default")
      (node (ref "SV3") (pin "1") (pinfunction "1_1") (pintype "passive"))
    )
    (net (code "6") (name "A1") (class "Default")
      (node (ref "SV3") (pin "2") (pinfunction "2_2") (pintype "passive"))
    )
    (net (code "7") (name "A2") (class "Default")
      (node (ref "SV3") (pin "3") (pinfunction "3_3") (pintype "passive"))
    )
    (net (code "8") (name "A3") (class "Default")
      (node (ref "SV3") (pin "4") (pinfunction "4_4") (pintype "passive"))
    )
    (net (code "9") (name "A4") (class "Default")
      (node (ref "SV3") (pin "5") (pinfunction "5_5") (pintype "passive"))
    )
    (net (code "10") (name "A5") (class "Default")
      (node (ref "SV3") (pin "6") (pinfunction "6_6") (pintype "passive"))
    )
    (net (code "11") (name "A6") (class "Default")
      (node (ref "FEATURE-CONN") (pin "4") (pinfunction "4_4") (pintype "passive"))
      (node (ref "SV3") (pin "7") (pinfunction "7_7") (pintype "passive"))
    )
    (net (code "12") (name "A7") (class "Default")
      (node (ref "FEATURE-CONN") (pin "3") (pinfunction "3_3") (pintype "passive"))
      (node (ref "SV3") (pin "8") (pinfunction "8_8") (pintype "passive"))
    )
    (net (code "13") (name "A8") (class "Default")
      (node (ref "R71") (pin "1") (pinfunction "1_1") (pintype "passive"))
      (node (ref "SV5") (pin "1") (pinfunction "1_1") (pintype "passive"))
    )
    (net (code "14") (name "A9") (class "Default")
      (node (ref "R70") (pin "1") (pinfunction "1_1") (pintype "passive"))
      (node (ref "SV5") (pin "2") (pinfunction "2_2") (pintype "passive"))
    )
    (net (code "15") (name "A10") (class "Default")
      (node (ref "R69") (pin "1") (pinfunction "1_1") (pintype "passive"))
      (node (ref "SV5") (pin "3") (pinfunction "3_3") (pintype "passive"))
    )
    (net (code "16") (name "A11") (class "Default")
      (node (ref "R68") (pin "1") (pinfunction "1_1") (pintype "passive"))
      (node (ref "SV5") (pin "4") (pinfunction "4_4") (pintype "passive"))
    )
    (net (code "17") (name "A12") (class "Default")
      (node (ref "R49") (pin "1") (pinfunction "1_1") (pintype "passive"))
      (node (ref "SV5") (pin "5") (pinfunction "5_5") (pintype "passive"))
    )
    (net (code "18") (name "A13") (class "Default")
      (node (ref "R48") (pin "1") (pinfunction "1_1") (pintype "passive"))
      (node (ref "SV5") (pin "6") (pinfunction "6_6") (pintype "passive"))
    )
    (net (code "19") (name "A14") (class "Default")
      (node (ref "R47") (pin "1") (pinfunction "1_1") (pintype "passive"))
      (node (ref "SV5") (pin "7") (pinfunction "7_7") (pintype "passive"))
    )
    (net (code "20") (name "A15") (class "Default")
      (node (ref "R46") (pin "1") (pinfunction "1_1") (pintype "passive"))
      (node (ref "SV5") (pin "8") (pinfunction "8_8") (pintype "passive"))
    )
    (net (code "21") (name "DIR-TFT") (class "Default")
      (node (ref "FEATURE-CONN") (pin "12") (pinfunction "12_12") (pintype "passive"))
      (node (ref "SV4") (pin "7") (pinfunction "7_7") (pintype "passive"))
    )
    (net (code "22") (name "GND") (class "Default")
      (node (ref "C1") (pin "-") (pinfunction "-_-") (pintype "passive"))
      (node (ref "C16") (pin "2") (pinfunction "2_2") (pintype "passive"))
      (node (ref "C17") (pin "2") (pinfunction "2_2") (pintype "passive"))
      (node (ref "C2") (pin "1") (pinfunction "1_1") (pintype "passive"))
      (node (ref "C3") (pin "-") (pinfunction "-_-") (pintype "passive"))
      (node (ref "C4") (pin "2") (pinfunction "2_2") (pintype "passive"))
      (node (ref "C5") (pin "-") (pinfunction "-_-") (pintype "passive"))
      (node (ref "C7") (pin "-") (pinfunction "-_-") (pintype "passive"))
      (node (ref "CONN") (pin "K") (pinfunction "C_K") (pintype "passive"))
      (node (ref "FEATURE-CONN") (pin "1") (pinfunction "1_1") (pintype "passive"))
      (node (ref "FEATURE-CONN") (pin "20") (pinfunction "20_20") (pintype "passive"))
      (node (ref "FEATURE-CONN") (pin "9") (pinfunction "9_9") (pintype "passive"))
      (node (ref "H1") (pin "B3,2") (pinfunction "MOUNT_B3,2") (pintype "passive"))
      (node (ref "HTBT") (pin "K") (pinfunction "C_K") (pintype "passive"))
      (node (ref "IC1") (pin "8") (pinfunction "GND_8") (pintype "power_in"))
      (node (ref "IC2") (pin "11") (pinfunction "VEE_11") (pintype "bidirectional"))
      (node (ref "IC3") (pin "11") (pinfunction "VEE_11") (pintype "bidirectional"))
      (node (ref "J10") (pin "1") (pinfunction "._1") (pintype "passive"))
      (node (ref "J11") (pin "1") (pinfunction "._1") (pintype "passive"))
      (node (ref "J12") (pin "1") (pinfunction "._1") (pintype "passive"))
      (node (ref "J9") (pin "1") (pinfunction "._1") (pintype "passive"))
      (node (ref "JP2") (pin "1") (pinfunction "._1") (pintype "passive"))
      (node (ref "JP4") (pin "1") (pinfunction "._1") (pintype "passive"))
      (node (ref "LED1") (pin "K") (pinfunction "C_K") (pintype "passive"))
      (node (ref "LED2") (pin "K") (pinfunction "C_K") (pintype "passive"))
      (node (ref "LED3") (pin "K") (pinfunction "C_K") (pintype "passive"))
      (node (ref "LED4") (pin "K") (pinfunction "C_K") (pintype "passive"))
      (node (ref "LED5") (pin "K") (pinfunction "C_K") (pintype "passive"))
      (node (ref "LED6") (pin "K") (pinfunction "C_K") (pintype "passive"))
      (node (ref "LED7") (pin "K") (pinfunction "C_K") (pintype "passive"))
      (node (ref "PE") (pin "1") (pinfunction "._1") (pintype "passive"))
      (node (ref "PUB") (pin "K") (pinfunction "C_K") (pintype "passive"))
      (node (ref "R32") (pin "2") (pinfunction "2_2") (pintype "passive"))
      (node (ref "R9") (pin "A") (pinfunction "A_A") (pintype "passive"))
      (node (ref "R9") (pin "S1") (pinfunction "S_S1") (pintype "passive"))
      (node (ref "R9") (pin "S2") (pinfunction "S_S2") (pintype "passive"))
      (node (ref "SUB") (pin "K") (pinfunction "C_K") (pintype "passive"))
      (node (ref "SV1") (pin "7") (pinfunction "7_7") (pintype "passive"))
      (node (ref "SV2") (pin "6") (pinfunction "6_6") (pintype "passive"))
      (node (ref "SV2") (pin "7") (pinfunction "7_7") (pintype "passive"))
      (node (ref "SV7") (pin "1") (pinfunction "1_1") (pintype "passive"))
      (node (ref "SV7") (pin "2") (pinfunction "2_2") (pintype "passive"))
      (node (ref "T10") (pin "1") (pinfunction "._1") (pintype "passive"))
      (node (ref "T13") (pin "1") (pinfunction "._1") (pintype "passive"))
      (node (ref "T17") (pin "1") (pinfunction "._1") (pintype "passive"))
      (node (ref "T18") (pin "1") (pinfunction "._1") (pintype "passive"))
      (node (ref "T22") (pin "1") (pinfunction "._1") (pintype "passive"))
      (node (ref "T35") (pin "1") (pinfunction "._1") (pintype "passive"))
      (node (ref "T36") (pin "1") (pinfunction "._1") (pintype "passive"))
      (node (ref "T7") (pin "1") (pinfunction "._1") (pintype "passive"))
      (node (ref "TR1") (pin "4") (pinfunction "4_4") (pintype "bidirectional"))
      (node (ref "TR1") (pin "5") (pinfunction "5_5") (pintype "bidirectional"))
      (node (ref "U1") (pin "GND") (pinfunction "GND_GND") (pintype "power_in"))
    )
    (net (code "23") (name "LED-GREEN-1") (class "Default")
      (node (ref "R11") (pin "1") (pinfunction "1_1") (pintype "passive"))
      (node (ref "T21") (pin "1") (pinfunction "._1") (pintype "passive"))
    )
    (net (code "24") (name "LED-GREEN-2") (class "Default")
      (node (ref "R15") (pin "1") (pinfunction "1_1") (pintype "passive"))
      (node (ref "T25") (pin "1") (pinfunction "._1") (pintype "passive"))
    )
    (net (code "25") (name "LED-RED-1") (class "Default")
      (node (ref "R10") (pin "1") (pinfunction "1_1") (pintype "passive"))
      (node (ref "T20") (pin "1") (pinfunction "._1") (pintype "passive"))
    )
    (net (code "26") (name "LED-RED-2") (class "Default")
      (node (ref "R14") (pin "1") (pinfunction "1_1") (pintype "passive"))
      (node (ref "T24") (pin "1") (pinfunction "._1") (pintype "passive"))
    )
    (net (code "27") (name "MISO") (class "Default")
      (node (ref "FEATURE-CONN") (pin "5") (pinfunction "5_5") (pintype "passive"))
      (node (ref "SV7") (pin "6") (pinfunction "6_6") (pintype "passive"))
    )
    (net (code "28") (name "MOSI") (class "Default")
      (node (ref "FEATURE-CONN") (pin "7") (pinfunction "7_7") (pintype "passive"))
      (node (ref "SV7") (pin "5") (pinfunction "5_5") (pintype "passive"))
    )
    (net (code "29") (name "Net-(C2-Pad2)") (class "Default")
      (node (ref "C2") (pin "2") (pinfunction "2_2") (pintype "passive"))
      (node (ref "R8") (pin "2") (pinfunction "2_2") (pintype "passive"))
      (node (ref "SV7") (pin "30") (pinfunction "30_30") (pintype "passive"))
    )
    (net (code "30") (name "Net-(C4-Pad1)") (class "Default")
      (node (ref "C4") (pin "1") (pinfunction "1_1") (pintype "passive"))
      (node (ref "R13") (pin "2") (pinfunction "2_2") (pintype "passive"))
      (node (ref "SV7") (pin "29") (pinfunction "29_29") (pintype "passive"))
    )
    (net (code "31") (name "Net-(C6-Pad+)") (class "Default")
      (node (ref "C6") (pin "+") (pinfunction "+_+") (pintype "passive"))
      (node (ref "R27") (pin "2") (pinfunction "2_2") (pintype "passive"))
    )
    (net (code "32") (name "Net-(C8-Pad1)") (class "Default")
      (node (ref "C8") (pin "1") (pinfunction "1_1") (pintype "passive"))
      (node (ref "R33") (pin "1") (pinfunction "1_1") (pintype "passive"))
      (node (ref "R38") (pin "2") (pinfunction "2_2") (pintype "passive"))
      (node (ref "R39") (pin "2") (pinfunction "2_2") (pintype "passive"))
    )
    (net (code "33") (name "Net-(C9-Pad1)") (class "Default")
      (node (ref "C9") (pin "1") (pinfunction "1_1") (pintype "passive"))
      (node (ref "R34") (pin "1") (pinfunction "1_1") (pintype "passive"))
      (node (ref "R40") (pin "2") (pinfunction "2_2") (pintype "passive"))
      (node (ref "R41") (pin "2") (pinfunction "2_2") (pintype "passive"))
    )
    (net (code "34") (name "Net-(C10-Pad1)") (class "Default")
      (node (ref "C10") (pin "1") (pinfunction "1_1") (pintype "passive"))
      (node (ref "R35") (pin "1") (pinfunction "1_1") (pintype "passive"))
      (node (ref "R42") (pin "2") (pinfunction "2_2") (pintype "passive"))
      (node (ref "R43") (pin "2") (pinfunction "2_2") (pintype "passive"))
    )
    (net (code "35") (name "Net-(C11-Pad1)") (class "Default")
      (node (ref "C11") (pin "1") (pinfunction "1_1") (pintype "passive"))
      (node (ref "R36") (pin "1") (pinfunction "1_1") (pintype "passive"))
      (node (ref "R44") (pin "2") (pinfunction "2_2") (pintype "passive"))
      (node (ref "R45") (pin "2") (pinfunction "2_2") (pintype "passive"))
    )
    (net (code "36") (name "Net-(C18-Pad+)") (class "Default")
      (node (ref "C18") (pin "+") (pinfunction "+_+") (pintype "passive"))
      (node (ref "R55") (pin "2") (pinfunction "2_2") (pintype "passive"))
      (node (ref "R59") (pin "2") (pinfunction "2_2") (pintype "passive"))
    )
    (net (code "37") (name "Net-(C18-Pad-)") (class "Default")
      (node (ref "C18") (pin "-") (pinfunction "-_-") (pintype "passive"))
      (node (ref "R51") (pin "2") (pinfunction "2_2") (pintype "passive"))
    )
    (net (code "38") (name "Net-(C19-Pad1)") (class "Default")
      (node (ref "C19") (pin "1") (pinfunction "1_1") (pintype "passive"))
      (node (ref "R56") (pin "1") (pinfunction "1_1") (pintype "passive"))
      (node (ref "R60") (pin "2") (pinfunction "2_2") (pintype "passive"))
      (node (ref "R61") (pin "2") (pinfunction "2_2") (pintype "passive"))
    )
    (net (code "39") (name "Net-(C20-Pad1)") (class "Default")
      (node (ref "C20") (pin "1") (pinfunction "1_1") (pintype "passive"))
      (node (ref "R57") (pin "1") (pinfunction "1_1") (pintype "passive"))
      (node (ref "R62") (pin "2") (pinfunction "2_2") (pintype "passive"))
      (node (ref "R63") (pin "2") (pinfunction "2_2") (pintype "passive"))
    )
    (net (code "40") (name "Net-(C21-Pad1)") (class "Default")
      (node (ref "C21") (pin "1") (pinfunction "1_1") (pintype "passive"))
      (node (ref "R58") (pin "1") (pinfunction "1_1") (pintype "passive"))
      (node (ref "R64") (pin "2") (pinfunction "2_2") (pintype "passive"))
      (node (ref "R65") (pin "2") (pinfunction "2_2") (pintype "passive"))
    )
    (net (code "41") (name "Net-(C22-Pad1)") (class "Default")
      (node (ref "C22") (pin "1") (pinfunction "1_1") (pintype "passive"))
      (node (ref "R59") (pin "1") (pinfunction "1_1") (pintype "passive"))
      (node (ref "R66") (pin "2") (pinfunction "2_2") (pintype "passive"))
      (node (ref "R67") (pin "2") (pinfunction "2_2") (pintype "passive"))
    )
    (net (code "42") (name "Net-(CONN-PadA)") (class "Default")
      (node (ref "CONN") (pin "A") (pinfunction "A_A") (pintype "passive"))
      (node (ref "R23") (pin "1") (pinfunction "1_1") (pintype "passive"))
    )
    (net (code "43") (name "Net-(D2-PadA)") (class "Default")
      (node (ref "D2") (pin "A") (pinfunction "A_A") (pintype "passive"))
      (node (ref "TR1") (pin "6") (pinfunction "6_6") (pintype "bidirectional"))
    )
    (net (code "44") (name "Net-(F1-1)") (class "Default")
      (node (ref "F1") (pin "P$1") (pinfunction "1_P$1") (pintype "passive"))
      (node (ref "T1") (pin "1") (pinfunction "._1") (pintype "passive"))
    )
    (net (code "45") (name "Net-(F1-2)") (class "Default")
      (node (ref "F1") (pin "P$2") (pinfunction "2_P$2") (pintype "passive"))
      (node (ref "T2") (pin "1") (pinfunction "._1") (pintype "passive"))
      (node (ref "TR1") (pin "1") (pinfunction "1_1") (pintype "bidirectional"))
    )
    (net (code "46") (name "Net-(HTBT-PadA)") (class "Default")
      (node (ref "HTBT") (pin "A") (pinfunction "A_A") (pintype "passive"))
      (node (ref "R26") (pin "1") (pinfunction "1_1") (pintype "passive"))
    )
    (net (code "47") (name "Net-(IC1-CD+)") (class "Default")
      (node (ref "C5") (pin "+") (pinfunction "+_+") (pintype "passive"))
      (node (ref "IC1") (pin "9") (pinfunction "CD+_9") (pintype "passive"))
      (node (ref "T33") (pin "1") (pinfunction "._1") (pintype "passive"))
      (node (ref "T34") (pin "1") (pinfunction "._1") (pintype "passive"))
    )
    (net (code "48") (name "Net-(IC1-O1)") (class "Default")
      (node (ref "IC1") (pin "16") (pinfunction "O1_16") (pintype "open_collector"))
      (node (ref "T26") (pin "1") (pinfunction "._1") (pintype "passive"))
    )
    (net (code "49") (name "Net-(IC1-O2)") (class "Default")
      (node (ref "IC1") (pin "15") (pinfunction "O2_15") (pintype "open_collector"))
      (node (ref "T27") (pin "1") (pinfunction "._1") (pintype "passive"))
    )
    (net (code "50") (name "Net-(IC1-O3)") (class "Default")
      (node (ref "IC1") (pin "14") (pinfunction "O3_14") (pintype "open_collector"))
      (node (ref "T28") (pin "1") (pinfunction "._1") (pintype "passive"))
    )
    (net (code "51") (name "Net-(IC1-O4)") (class "Default")
      (node (ref "IC1") (pin "13") (pinfunction "O4_13") (pintype "open_collector"))
      (node (ref "T29") (pin "1") (pinfunction "._1") (pintype "passive"))
    )
    (net (code "52") (name "Net-(IC1-O5)") (class "Default")
      (node (ref "IC1") (pin "12") (pinfunction "O5_12") (pintype "open_collector"))
      (node (ref "T30") (pin "1") (pinfunction "._1") (pintype "passive"))
    )
    (net (code "53") (name "Net-(IC1-O6)") (class "Default")
      (node (ref "IC1") (pin "11") (pinfunction "O6_11") (pintype "open_collector"))
      (node (ref "T31") (pin "1") (pinfunction "._1") (pintype "passive"))
    )
    (net (code "54") (name "Net-(IC1-O7)") (class "Default")
      (node (ref "IC1") (pin "10") (pinfunction "O7_10") (pintype "open_collector"))
      (node (ref "T32") (pin "1") (pinfunction "._1") (pintype "passive"))
    )
    (net (code "55") (name "Net-(IC2A-+IN)") (class "Default")
      (node (ref "C10") (pin "2") (pinfunction "2_2") (pintype "passive"))
      (node (ref "C11") (pin "2") (pinfunction "2_2") (pintype "passive"))
      (node (ref "C19") (pin "2") (pinfunction "2_2") (pintype "passive"))
      (node (ref "C20") (pin "2") (pinfunction "2_2") (pintype "passive"))
      (node (ref "C21") (pin "2") (pinfunction "2_2") (pintype "passive"))
      (node (ref "C22") (pin "2") (pinfunction "2_2") (pintype "passive"))
      (node (ref "C7") (pin "+") (pinfunction "+_+") (pintype "passive"))
      (node (ref "C8") (pin "2") (pinfunction "2_2") (pintype "passive"))
      (node (ref "C9") (pin "2") (pinfunction "2_2") (pintype "passive"))
      (node (ref "IC2") (pin "10") (pinfunction "+IN_10") (pintype "input"))
      (node (ref "IC2") (pin "12") (pinfunction "+IN_12") (pintype "input"))
      (node (ref "IC2") (pin "3") (pinfunction "+IN_3") (pintype "input"))
      (node (ref "IC2") (pin "5") (pinfunction "+IN_5") (pintype "input"))
      (node (ref "IC3") (pin "10") (pinfunction "+IN_10") (pintype "input"))
      (node (ref "IC3") (pin "12") (pinfunction "+IN_12") (pintype "input"))
      (node (ref "IC3") (pin "3") (pinfunction "+IN_3") (pintype "input"))
      (node (ref "IC3") (pin "5") (pinfunction "+IN_5") (pintype "input"))
      (node (ref "R28") (pin "1") (pinfunction "1_1") (pintype "passive"))
      (node (ref "R29") (pin "1") (pinfunction "1_1") (pintype "passive"))
      (node (ref "R30") (pin "1") (pinfunction "1_1") (pintype "passive"))
      (node (ref "R31") (pin "1") (pinfunction "1_1") (pintype "passive"))
      (node (ref "R32") (pin "1") (pinfunction "1_1") (pintype "passive"))
      (node (ref "R37") (pin "1") (pinfunction "1_1") (pintype "passive"))
      (node (ref "R52") (pin "1") (pinfunction "1_1") (pintype "passive"))
      (node (ref "R53") (pin "1") (pinfunction "1_1") (pintype "passive"))
      (node (ref "R54") (pin "1") (pinfunction "1_1") (pintype "passive"))
      (node (ref "R55") (pin "1") (pinfunction "1_1") (pintype "passive"))
      (node (ref "T38") (pin "1") (pinfunction "._1") (pintype "passive"))
      (node (ref "T40") (pin "1") (pinfunction "._1") (pintype "passive"))
      (node (ref "T42") (pin "1") (pinfunction "._1") (pintype "passive"))
      (node (ref "T44") (pin "1") (pinfunction "._1") (pintype "passive"))
      (node (ref "T46") (pin "1") (pinfunction "._1") (pintype "passive"))
      (node (ref "T48") (pin "1") (pinfunction "._1") (pintype "passive"))
      (node (ref "T50") (pin "1") (pinfunction "._1") (pintype "passive"))
    )
    (net (code "56") (name "Net-(IC2A--IN)") (class "Default")
      (node (ref "C12") (pin "1") (pinfunction "1_1") (pintype "passive"))
      (node (ref "IC2") (pin "2") (pinfunction "-IN_2") (pintype "input"))
      (node (ref "R39") (pin "1") (pinfunction "1_1") (pintype "passive"))
    )
    (net (code "57") (name "Net-(IC2A-OUT)") (class "Default")
      (node (ref "C12") (pin "2") (pinfunction "2_2") (pintype "passive"))
      (node (ref "IC2") (pin "1") (pinfunction "OUT_1") (pintype "output"))
      (node (ref "R38") (pin "1") (pinfunction "1_1") (pintype "passive"))
      (node (ref "R46") (pin "2") (pinfunction "2_2") (pintype "passive"))
    )
    (net (code "58") (name "Net-(IC2B--IN)") (class "Default")
      (node (ref "C13") (pin "1") (pinfunction "1_1") (pintype "passive"))
      (node (ref "IC2") (pin "6") (pinfunction "-IN_6") (pintype "input"))
      (node (ref "R41") (pin "1") (pinfunction "1_1") (pintype "passive"))
    )
    (net (code "59") (name "Net-(IC2B-OUT)") (class "Default")
      (node (ref "C13") (pin "2") (pinfunction "2_2") (pintype "passive"))
      (node (ref "IC2") (pin "7") (pinfunction "OUT_7") (pintype "output"))
      (node (ref "R40") (pin "1") (pinfunction "1_1") (pintype "passive"))
      (node (ref "R47") (pin "2") (pinfunction "2_2") (pintype "passive"))
    )
    (net (code "60") (name "Net-(IC2C--IN)") (class "Default")
      (node (ref "C14") (pin "1") (pinfunction "1_1") (pintype "passive"))
      (node (ref "IC2") (pin "9") (pinfunction "-IN_9") (pintype "input"))
      (node (ref "R43") (pin "1") (pinfunction "1_1") (pintype "passive"))
    )
    (net (code "61") (name "Net-(IC2C-OUT)") (class "Default")
      (node (ref "C14") (pin "2") (pinfunction "2_2") (pintype "passive"))
      (node (ref "IC2") (pin "8") (pinfunction "OUT_8") (pintype "output"))
      (node (ref "R42") (pin "1") (pinfunction "1_1") (pintype "passive"))
      (node (ref "R48") (pin "2") (pinfunction "2_2") (pintype "passive"))
    )
    (net (code "62") (name "Net-(IC2D--IN)") (class "Default")
      (node (ref "C15") (pin "1") (pinfunction "1_1") (pintype "passive"))
      (node (ref "IC2") (pin "13") (pinfunction "-IN_13") (pintype "input"))
      (node (ref "R45") (pin "1") (pinfunction "1_1") (pintype "passive"))
    )
    (net (code "63") (name "Net-(IC2D-OUT)") (class "Default")
      (node (ref "C15") (pin "2") (pinfunction "2_2") (pintype "passive"))
      (node (ref "IC2") (pin "14") (pinfunction "OUT_14") (pintype "output"))
      (node (ref "R44") (pin "1") (pinfunction "1_1") (pintype "passive"))
      (node (ref "R49") (pin "2") (pinfunction "2_2") (pintype "passive"))
    )
    (net (code "64") (name "Net-(IC2E-VDD)") (class "Default")
      (node (ref "C16") (pin "1") (pinfunction "1_1") (pintype "passive"))
      (node (ref "C17") (pin "1") (pinfunction "1_1") (pintype "passive"))
      (node (ref "D3") (pin "A") (pinfunction "A_A") (pintype "passive"))
      (node (ref "IC2") (pin "4") (pinfunction "VDD_4") (pintype "bidirectional"))
      (node (ref "IC3") (pin "4") (pinfunction "VDD_4") (pintype "bidirectional"))
      (node (ref "R50") (pin "1") (pinfunction "1_1") (pintype "passive"))
    )
    (net (code "65") (name "Net-(IC3A--IN)") (class "Default")
      (node (ref "C23") (pin "1") (pinfunction "1_1") (pintype "passive"))
      (node (ref "IC3") (pin "2") (pinfunction "-IN_2") (pintype "input"))
      (node (ref "R61") (pin "1") (pinfunction "1_1") (pintype "passive"))
    )
    (net (code "66") (name "Net-(IC3A-OUT)") (class "Default")
      (node (ref "C23") (pin "2") (pinfunction "2_2") (pintype "passive"))
      (node (ref "IC3") (pin "1") (pinfunction "OUT_1") (pintype "output"))
      (node (ref "R60") (pin "1") (pinfunction "1_1") (pintype "passive"))
      (node (ref "R68") (pin "2") (pinfunction "2_2") (pintype "passive"))
    )
    (net (code "67") (name "Net-(IC3B--IN)") (class "Default")
      (node (ref "C24") (pin "1") (pinfunction "1_1") (pintype "passive"))
      (node (ref "IC3") (pin "6") (pinfunction "-IN_6") (pintype "input"))
      (node (ref "R63") (pin "1") (pinfunction "1_1") (pintype "passive"))
    )
    (net (code "68") (name "Net-(IC3B-OUT)") (class "Default")
      (node (ref "C24") (pin "2") (pinfunction "2_2") (pintype "passive"))
      (node (ref "IC3") (pin "7") (pinfunction "OUT_7") (pintype "output"))
      (node (ref "R62") (pin "1") (pinfunction "1_1") (pintype "passive"))
      (node (ref "R69") (pin "2") (pinfunction "2_2") (pintype "passive"))
    )
    (net (code "69") (name "Net-(IC3C--IN)") (class "Default")
      (node (ref "C25") (pin "1") (pinfunction "1_1") (pintype "passive"))
      (node (ref "IC3") (pin "9") (pinfunction "-IN_9") (pintype "input"))
      (node (ref "R65") (pin "1") (pinfunction "1_1") (pintype "passive"))
    )
    (net (code "70") (name "Net-(IC3C-OUT)") (class "Default")
      (node (ref "C25") (pin "2") (pinfunction "2_2") (pintype "passive"))
      (node (ref "IC3") (pin "8") (pinfunction "OUT_8") (pintype "output"))
      (node (ref "R64") (pin "1") (pinfunction "1_1") (pintype "passive"))
      (node (ref "R70") (pin "2") (pinfunction "2_2") (pintype "passive"))
    )
    (net (code "71") (name "Net-(IC3D--IN)") (class "Default")
      (node (ref "C26") (pin "1") (pinfunction "1_1") (pintype "passive"))
      (node (ref "IC3") (pin "13") (pinfunction "-IN_13") (pintype "input"))
      (node (ref "R67") (pin "1") (pinfunction "1_1") (pintype "passive"))
    )
    (net (code "72") (name "Net-(IC3D-OUT)") (class "Default")
      (node (ref "C26") (pin "2") (pinfunction "2_2") (pintype "passive"))
      (node (ref "IC3") (pin "14") (pinfunction "OUT_14") (pintype "output"))
      (node (ref "R66") (pin "1") (pinfunction "1_1") (pintype "passive"))
      (node (ref "R71") (pin "2") (pinfunction "2_2") (pintype "passive"))
    )
    (net (code "73") (name "Net-(LED1-PadA)") (class "Default")
      (node (ref "LED1") (pin "A") (pinfunction "A_A") (pintype "passive"))
      (node (ref "R16") (pin "1") (pinfunction "1_1") (pintype "passive"))
    )
    (net (code "74") (name "Net-(LED2-PadA)") (class "Default")
      (node (ref "LED2") (pin "A") (pinfunction "A_A") (pintype "passive"))
      (node (ref "R17") (pin "1") (pinfunction "1_1") (pintype "passive"))
    )
    (net (code "75") (name "Net-(LED3-PadA)") (class "Default")
      (node (ref "LED3") (pin "A") (pinfunction "A_A") (pintype "passive"))
      (node (ref "R18") (pin "1") (pinfunction "1_1") (pintype "passive"))
    )
    (net (code "76") (name "Net-(LED4-PadA)") (class "Default")
      (node (ref "LED4") (pin "A") (pinfunction "A_A") (pintype "passive"))
      (node (ref "R19") (pin "1") (pinfunction "1_1") (pintype "passive"))
    )
    (net (code "77") (name "Net-(LED5-PadA)") (class "Default")
      (node (ref "LED5") (pin "A") (pinfunction "A_A") (pintype "passive"))
      (node (ref "R20") (pin "1") (pinfunction "1_1") (pintype "passive"))
    )
    (net (code "78") (name "Net-(LED6-PadA)") (class "Default")
      (node (ref "LED6") (pin "A") (pinfunction "A_A") (pintype "passive"))
      (node (ref "R21") (pin "1") (pinfunction "1_1") (pintype "passive"))
    )
    (net (code "79") (name "Net-(LED7-PadA)") (class "Default")
      (node (ref "LED7") (pin "A") (pinfunction "A_A") (pintype "passive"))
      (node (ref "R22") (pin "1") (pinfunction "1_1") (pintype "passive"))
    )
    (net (code "80") (name "Net-(PUB-PadA)") (class "Default")
      (node (ref "PUB") (pin "A") (pinfunction "A_A") (pintype "passive"))
      (node (ref "R24") (pin "1") (pinfunction "1_1") (pintype "passive"))
    )
    (net (code "81") (name "Net-(Q1-B)") (class "Default")
      (node (ref "Q1") (pin "2") (pinfunction "B_2") (pintype "passive"))
      (node (ref "R2") (pin "2") (pinfunction "2_2") (pintype "passive"))
      (node (ref "R3") (pin "1") (pinfunction "1_1") (pintype "passive"))
    )
    (net (code "82") (name "Net-(Q1-C)") (class "Default")
      (node (ref "Q1") (pin "3") (pinfunction "C_3") (pintype "passive"))
      (node (ref "T11") (pin "1") (pinfunction "._1") (pintype "passive"))
    )
    (net (code "83") (name "Net-(R3-Pad2)") (class "Default")
      (node (ref "R3") (pin "2") (pinfunction "2_2") (pintype "passive"))
      (node (ref "SV4") (pin "3") (pinfunction "3_3") (pintype "passive"))
    )
    (net (code "84") (name "Net-(R7-Pad1)") (class "Default")
      (node (ref "R7") (pin "1") (pinfunction "1_1") (pintype "passive"))
      (node (ref "R9") (pin "E") (pinfunction "E_E") (pintype "passive"))
    )
    (net (code "85") (name "Net-(R7-Pad2)") (class "Default")
      (node (ref "R7") (pin "2") (pinfunction "2_2") (pintype "passive"))
      (node (ref "U1") (pin "TR") (pinfunction "TR_TR") (pintype "input"))
    )
    (net (code "86") (name "Net-(R10-Pad2)") (class "Default")
      (node (ref "R10") (pin "2") (pinfunction "2_2") (pintype "passive"))
      (node (ref "SV7") (pin "32") (pinfunction "32_32") (pintype "passive"))
    )
    (net (code "87") (name "Net-(R11-Pad2)") (class "Default")
      (node (ref "R11") (pin "2") (pinfunction "2_2") (pintype "passive"))
      (node (ref "SV7") (pin "34") (pinfunction "34_34") (pintype "passive"))
    )
    (net (code "88") (name "Net-(R14-Pad2)") (class "Default")
      (node (ref "R14") (pin "2") (pinfunction "2_2") (pintype "passive"))
      (node (ref "SV7") (pin "31") (pinfunction "31_31") (pintype "passive"))
    )
    (net (code "89") (name "Net-(R15-Pad2)") (class "Default")
      (node (ref "R15") (pin "2") (pinfunction "2_2") (pintype "passive"))
      (node (ref "SV7") (pin "33") (pinfunction "33_33") (pintype "passive"))
    )
    (net (code "90") (name "Net-(R25-Pad1)") (class "Default")
      (node (ref "R25") (pin "1") (pinfunction "1_1") (pintype "passive"))
      (node (ref "SUB") (pin "A") (pinfunction "A_A") (pintype "passive"))
    )
    (net (code "91") (name "Net-(R27-Pad1)") (class "Default")
      (node (ref "R27") (pin "1") (pinfunction "1_1") (pintype "passive"))
      (node (ref "R28") (pin "2") (pinfunction "2_2") (pintype "passive"))
      (node (ref "R33") (pin "2") (pinfunction "2_2") (pintype "passive"))
    )
    (net (code "92") (name "Net-(T3-.)") (class "Default")
      (node (ref "T3") (pin "1") (pinfunction "._1") (pintype "passive"))
      (node (ref "T4") (pin "1") (pinfunction "._1") (pintype "passive"))
      (node (ref "TR1") (pin "2") (pinfunction "2_2") (pintype "bidirectional"))
    )
    (net (code "93") (name "Net-(T37-.)") (class "Default")
      (node (ref "R29") (pin "2") (pinfunction "2_2") (pintype "passive"))
      (node (ref "R34") (pin "2") (pinfunction "2_2") (pintype "passive"))
      (node (ref "T37") (pin "1") (pinfunction "._1") (pintype "passive"))
    )
    (net (code "94") (name "Net-(T39-.)") (class "Default")
      (node (ref "R30") (pin "2") (pinfunction "2_2") (pintype "passive"))
      (node (ref "R35") (pin "2") (pinfunction "2_2") (pintype "passive"))
      (node (ref "T39") (pin "1") (pinfunction "._1") (pintype "passive"))
    )
    (net (code "95") (name "Net-(T41-.)") (class "Default")
      (node (ref "R31") (pin "2") (pinfunction "2_2") (pintype "passive"))
      (node (ref "R36") (pin "2") (pinfunction "2_2") (pintype "passive"))
      (node (ref "T41") (pin "1") (pinfunction "._1") (pintype "passive"))
    )
    (net (code "96") (name "Net-(T43-.)") (class "Default")
      (node (ref "R52") (pin "2") (pinfunction "2_2") (pintype "passive"))
      (node (ref "R56") (pin "2") (pinfunction "2_2") (pintype "passive"))
      (node (ref "T43") (pin "1") (pinfunction "._1") (pintype "passive"))
    )
    (net (code "97") (name "Net-(T45-.)") (class "Default")
      (node (ref "R53") (pin "2") (pinfunction "2_2") (pintype "passive"))
      (node (ref "R57") (pin "2") (pinfunction "2_2") (pintype "passive"))
      (node (ref "T45") (pin "1") (pinfunction "._1") (pintype "passive"))
    )
    (net (code "98") (name "Net-(T47-.)") (class "Default")
      (node (ref "R54") (pin "2") (pinfunction "2_2") (pintype "passive"))
      (node (ref "R58") (pin "2") (pinfunction "2_2") (pintype "passive"))
      (node (ref "T47") (pin "1") (pinfunction "._1") (pintype "passive"))
    )
    (net (code "99") (name "Net-(T49-.)") (class "Default")
      (node (ref "R51") (pin "1") (pinfunction "1_1") (pintype "passive"))
      (node (ref "T49") (pin "1") (pinfunction "._1") (pintype "passive"))
    )
    (net (code "100") (name "PA6") (class "Default")
      (node (ref "JP1") (pin "1") (pinfunction "._1") (pintype "passive"))
      (node (ref "SV7") (pin "28") (pinfunction "28_28") (pintype "passive"))
    )
    (net (code "101") (name "PA7") (class "Default")
      (node (ref "JP3") (pin "1") (pinfunction "._1") (pintype "passive"))
      (node (ref "SV7") (pin "27") (pinfunction "27_27") (pintype "passive"))
    )
    (net (code "102") (name "PB5") (class "Default")
      (node (ref "FEATURE-CONN") (pin "10") (pinfunction "10_10") (pintype "passive"))
      (node (ref "SV1") (pin "4") (pinfunction "4_4") (pintype "passive"))
    )
    (net (code "103") (name "PB6") (class "Default")
      (node (ref "FEATURE-CONN") (pin "8") (pinfunction "8_8") (pintype "passive"))
      (node (ref "SV1") (pin "5") (pinfunction "5_5") (pintype "passive"))
    )
    (net (code "104") (name "PC0") (class "Default")
      (node (ref "R26") (pin "2") (pinfunction "2_2") (pintype "passive"))
      (node (ref "SV7") (pin "19") (pinfunction "19_19") (pintype "passive"))
    )
    (net (code "105") (name "PC1") (class "Default")
      (node (ref "IC1") (pin "1") (pinfunction "I1_1") (pintype "input"))
      (node (ref "R16") (pin "2") (pinfunction "2_2") (pintype "passive"))
      (node (ref "SV7") (pin "20") (pinfunction "20_20") (pintype "passive"))
    )
    (net (code "106") (name "PC2") (class "Default")
      (node (ref "IC1") (pin "2") (pinfunction "I2_2") (pintype "input"))
      (node (ref "R17") (pin "2") (pinfunction "2_2") (pintype "passive"))
      (node (ref "SV7") (pin "21") (pinfunction "21_21") (pintype "passive"))
    )
    (net (code "107") (name "PC3") (class "Default")
      (node (ref "IC1") (pin "3") (pinfunction "I3_3") (pintype "input"))
      (node (ref "R18") (pin "2") (pinfunction "2_2") (pintype "passive"))
      (node (ref "SV7") (pin "22") (pinfunction "22_22") (pintype "passive"))
    )
    (net (code "108") (name "PC4") (class "Default")
      (node (ref "IC1") (pin "4") (pinfunction "I4_4") (pintype "input"))
      (node (ref "R19") (pin "2") (pinfunction "2_2") (pintype "passive"))
      (node (ref "SV7") (pin "23") (pinfunction "23_23") (pintype "passive"))
    )
    (net (code "109") (name "PC5") (class "Default")
      (node (ref "IC1") (pin "5") (pinfunction "I5_5") (pintype "input"))
      (node (ref "R20") (pin "2") (pinfunction "2_2") (pintype "passive"))
      (node (ref "SV7") (pin "24") (pinfunction "24_24") (pintype "passive"))
    )
    (net (code "110") (name "PC6") (class "Default")
      (node (ref "IC1") (pin "6") (pinfunction "I6_6") (pintype "input"))
      (node (ref "R21") (pin "2") (pinfunction "2_2") (pintype "passive"))
      (node (ref "SV7") (pin "25") (pinfunction "25_25") (pintype "passive"))
    )
    (net (code "111") (name "PC7") (class "Default")
      (node (ref "IC1") (pin "7") (pinfunction "I7_7") (pintype "input"))
      (node (ref "R22") (pin "2") (pinfunction "2_2") (pintype "passive"))
      (node (ref "SV7") (pin "26") (pinfunction "26_26") (pintype "passive"))
    )
    (net (code "112") (name "PD7") (class "Default")
      (node (ref "R25") (pin "2") (pinfunction "2_2") (pintype "passive"))
      (node (ref "SV7") (pin "18") (pinfunction "18_18") (pintype "passive"))
    )
    (net (code "113") (name "PG0") (class "Default")
      (node (ref "J1") (pin "1") (pinfunction "._1") (pintype "passive"))
      (node (ref "J2") (pin "1") (pinfunction "._1") (pintype "passive"))
      (node (ref "J3") (pin "1") (pinfunction "._1") (pintype "passive"))
      (node (ref "J4") (pin "1") (pinfunction "._1") (pintype "passive"))
      (node (ref "SV7") (pin "15") (pinfunction "15_15") (pintype "passive"))
    )
    (net (code "114") (name "PG1") (class "Default")
      (node (ref "R23") (pin "2") (pinfunction "2_2") (pintype "passive"))
      (node (ref "SV7") (pin "16") (pinfunction "16_16") (pintype "passive"))
    )
    (net (code "115") (name "PG2") (class "Default")
      (node (ref "R24") (pin "2") (pinfunction "2_2") (pintype "passive"))
      (node (ref "SV7") (pin "17") (pinfunction "17_17") (pintype "passive"))
    )
    (net (code "116") (name "PL0") (class "Default")
      (node (ref "J8") (pin "1") (pinfunction "._1") (pintype "passive"))
      (node (ref "SV7") (pin "7") (pinfunction "7_7") (pintype "passive"))
    )
    (net (code "117") (name "PL1") (class "Default")
      (node (ref "J7") (pin "1") (pinfunction "._1") (pintype "passive"))
      (node (ref "SV7") (pin "8") (pinfunction "8_8") (pintype "passive"))
    )
    (net (code "118") (name "PL2") (class "Default")
      (node (ref "J6") (pin "1") (pinfunction "._1") (pintype "passive"))
      (node (ref "SV7") (pin "9") (pinfunction "9_9") (pintype "passive"))
    )
    (net (code "119") (name "PL3") (class "Default")
      (node (ref "J5") (pin "1") (pinfunction "._1") (pintype "passive"))
      (node (ref "SV7") (pin "10") (pinfunction "10_10") (pintype "passive"))
    )
    (net (code "120") (name "PL4") (class "Default")
      (node (ref "FEATURE-CONN") (pin "13") (pinfunction "13_13") (pintype "passive"))
      (node (ref "SV7") (pin "11") (pinfunction "11_11") (pintype "passive"))
    )
    (net (code "121") (name "PL5") (class "Default")
      (node (ref "FEATURE-CONN") (pin "11") (pinfunction "11_11") (pintype "passive"))
      (node (ref "SV7") (pin "12") (pinfunction "12_12") (pintype "passive"))
    )
    (net (code "122") (name "PL6") (class "Default")
      (node (ref "FEATURE-CONN") (pin "17") (pinfunction "17_17") (pintype "passive"))
      (node (ref "SV7") (pin "13") (pinfunction "13_13") (pintype "passive"))
    )
    (net (code "123") (name "PL7") (class "Default")
      (node (ref "FEATURE-CONN") (pin "15") (pinfunction "15_15") (pintype "passive"))
      (node (ref "SV7") (pin "14") (pinfunction "14_14") (pintype "passive"))
    )
    (net (code "124") (name "RESET") (class "Default")
      (node (ref "SV1") (pin "1") (pinfunction "1_1") (pintype "passive"))
      (node (ref "SV2") (pin "3") (pinfunction "3_3") (pintype "passive"))
    )
    (net (code "125") (name "RXD1") (class "Default")
      (node (ref "FEATURE-CONN") (pin "18") (pinfunction "18_18") (pintype "passive"))
      (node (ref "SV6") (pin "3") (pinfunction "3_3") (pintype "passive"))
    )
    (net (code "126") (name "RXD2") (class "Default")
      (node (ref "SV6") (pin "5") (pinfunction "5_5") (pintype "passive"))
    )
    (net (code "127") (name "RXD3") (class "Default")
      (node (ref "SV6") (pin "7") (pinfunction "7_7") (pintype "passive"))
      (node (ref "T12") (pin "1") (pinfunction "._1") (pintype "passive"))
    )
    (net (code "128") (name "SCK") (class "Default")
      (node (ref "FEATURE-CONN") (pin "6") (pinfunction "6_6") (pintype "passive"))
      (node (ref "SV7") (pin "4") (pinfunction "4_4") (pintype "passive"))
    )
    (net (code "129") (name "SCL") (class "Default")
      (node (ref "R5") (pin "2") (pinfunction "2_2") (pintype "passive"))
      (node (ref "SV6") (pin "1") (pinfunction "1_1") (pintype "passive"))
      (node (ref "T16") (pin "1") (pinfunction "._1") (pintype "passive"))
    )
    (net (code "130") (name "SDA") (class "Default")
      (node (ref "R4") (pin "2") (pinfunction "2_2") (pintype "passive"))
      (node (ref "SV6") (pin "2") (pinfunction "2_2") (pintype "passive"))
      (node (ref "T15") (pin "1") (pinfunction "._1") (pintype "passive"))
    )
    (net (code "131") (name "SEL-ETH") (class "Default")
      (node (ref "SV1") (pin "3") (pinfunction "3_3") (pintype "passive"))
    )
    (net (code "132") (name "SEL-TFT") (class "Default")
      (node (ref "FEATURE-CONN") (pin "14") (pinfunction "14_14") (pintype "passive"))
      (node (ref "SV4") (pin "6") (pinfunction "6_6") (pintype "passive"))
    )
    (net (code "133") (name "SWITCH-1") (class "Default")
      (node (ref "R6") (pin "2") (pinfunction "2_2") (pintype "passive"))
      (node (ref "R8") (pin "1") (pinfunction "1_1") (pintype "passive"))
      (node (ref "T19") (pin "1") (pinfunction "._1") (pintype "passive"))
    )
    (net (code "134") (name "SWITCH-2") (class "Default")
      (node (ref "R12") (pin "2") (pinfunction "2_2") (pintype "passive"))
      (node (ref "R13") (pin "1") (pinfunction "1_1") (pintype "passive"))
      (node (ref "T23") (pin "1") (pinfunction "._1") (pintype "passive"))
    )
    (net (code "135") (name "TXD1") (class "Default")
      (node (ref "FEATURE-CONN") (pin "16") (pinfunction "16_16") (pintype "passive"))
      (node (ref "SV6") (pin "4") (pinfunction "4_4") (pintype "passive"))
    )
    (net (code "136") (name "TXD2") (class "Default")
      (node (ref "SV6") (pin "6") (pinfunction "6_6") (pintype "passive"))
    )
    (net (code "137") (name "unconnected-(SPI-PASS-THROUGH-Pad1)") (class "Default")
      (node (ref "SPI-PASS-THROUGH") (pin "1") (pinfunction "1_1") (pintype "passive"))
    )
    (net (code "138") (name "unconnected-(SPI-PASS-THROUGH-Pad2)") (class "Default")
      (node (ref "SPI-PASS-THROUGH") (pin "2") (pinfunction "2_2") (pintype "passive"))
    )
    (net (code "139") (name "unconnected-(SPI-PASS-THROUGH-Pad3)") (class "Default")
      (node (ref "SPI-PASS-THROUGH") (pin "3") (pinfunction "3_3") (pintype "passive"))
    )
    (net (code "140") (name "unconnected-(SPI-PASS-THROUGH-Pad4)") (class "Default")
      (node (ref "SPI-PASS-THROUGH") (pin "4") (pinfunction "4_4") (pintype "passive"))
    )
    (net (code "141") (name "unconnected-(SPI-PASS-THROUGH-Pad5)") (class "Default")
      (node (ref "SPI-PASS-THROUGH") (pin "5") (pinfunction "5_5") (pintype "passive"))
    )
    (net (code "142") (name "unconnected-(SPI-PASS-THROUGH-Pad6)") (class "Default")
      (node (ref "SPI-PASS-THROUGH") (pin "6") (pinfunction "6_6") (pintype "passive"))
    )
    (net (code "143") (name "unconnected-(SV1-Pad2)") (class "Default")
      (node (ref "SV1") (pin "2") (pinfunction "2_2") (pintype "passive"))
    )
    (net (code "144") (name "unconnected-(SV1-Pad6)") (class "Default")
      (node (ref "SV1") (pin "6") (pinfunction "6_6") (pintype "passive"))
    )
    (net (code "145") (name "unconnected-(SV1-Pad8)") (class "Default")
      (node (ref "SV1") (pin "8") (pinfunction "8_8") (pintype "passive"))
    )
    (net (code "146") (name "unconnected-(SV1-Pad9)") (class "Default")
      (node (ref "SV1") (pin "9") (pinfunction "9_9") (pintype "passive"))
    )
    (net (code "147") (name "unconnected-(SV1-Pad10)") (class "Default")
      (node (ref "SV1") (pin "10") (pinfunction "10_10") (pintype "passive"))
    )
    (net (code "148") (name "unconnected-(SV2-Pad1)") (class "Default")
      (node (ref "SV2") (pin "1") (pinfunction "1_1") (pintype "passive"))
    )
    (net (code "149") (name "unconnected-(SV2-Pad2)") (class "Default")
      (node (ref "SV2") (pin "2") (pinfunction "2_2") (pintype "passive"))
    )
    (net (code "150") (name "unconnected-(SV2-Pad4)") (class "Default")
      (node (ref "SV2") (pin "4") (pinfunction "4_4") (pintype "passive"))
    )
    (net (code "151") (name "unconnected-(SV2-Pad8)") (class "Default")
      (node (ref "SV2") (pin "8") (pinfunction "8_8") (pintype "passive"))
    )
    (net (code "152") (name "unconnected-(SV4-Pad1)") (class "Default")
      (node (ref "SV4") (pin "1") (pinfunction "1_1") (pintype "passive"))
    )
    (net (code "153") (name "unconnected-(SV4-Pad2)") (class "Default")
      (node (ref "SV4") (pin "2") (pinfunction "2_2") (pintype "passive"))
    )
    (net (code "154") (name "unconnected-(SV4-Pad5)") (class "Default")
      (node (ref "SV4") (pin "5") (pinfunction "5_5") (pintype "passive"))
    )
    (net (code "155") (name "unconnected-(SV4-Pad8)") (class "Default")
      (node (ref "SV4") (pin "8") (pinfunction "8_8") (pintype "passive"))
    )
    (net (code "156") (name "unconnected-(SV6-Pad8)") (class "Default")
      (node (ref "SV6") (pin "8") (pinfunction "8_8") (pintype "passive"))
    )
    (net (code "157") (name "unconnected-(SV7-Pad3)") (class "Default")
      (node (ref "SV7") (pin "3") (pinfunction "3_3") (pintype "passive"))
    )
    (net (code "158") (name "unconnected-(U1-PadE)") (class "Default")
      (node (ref "U1") (pin "E") (pinfunction "E_E") (pintype "input"))
    )
  )
)
